# M8655B.net
KiCad netlist of a schematic drawn in EAGLE
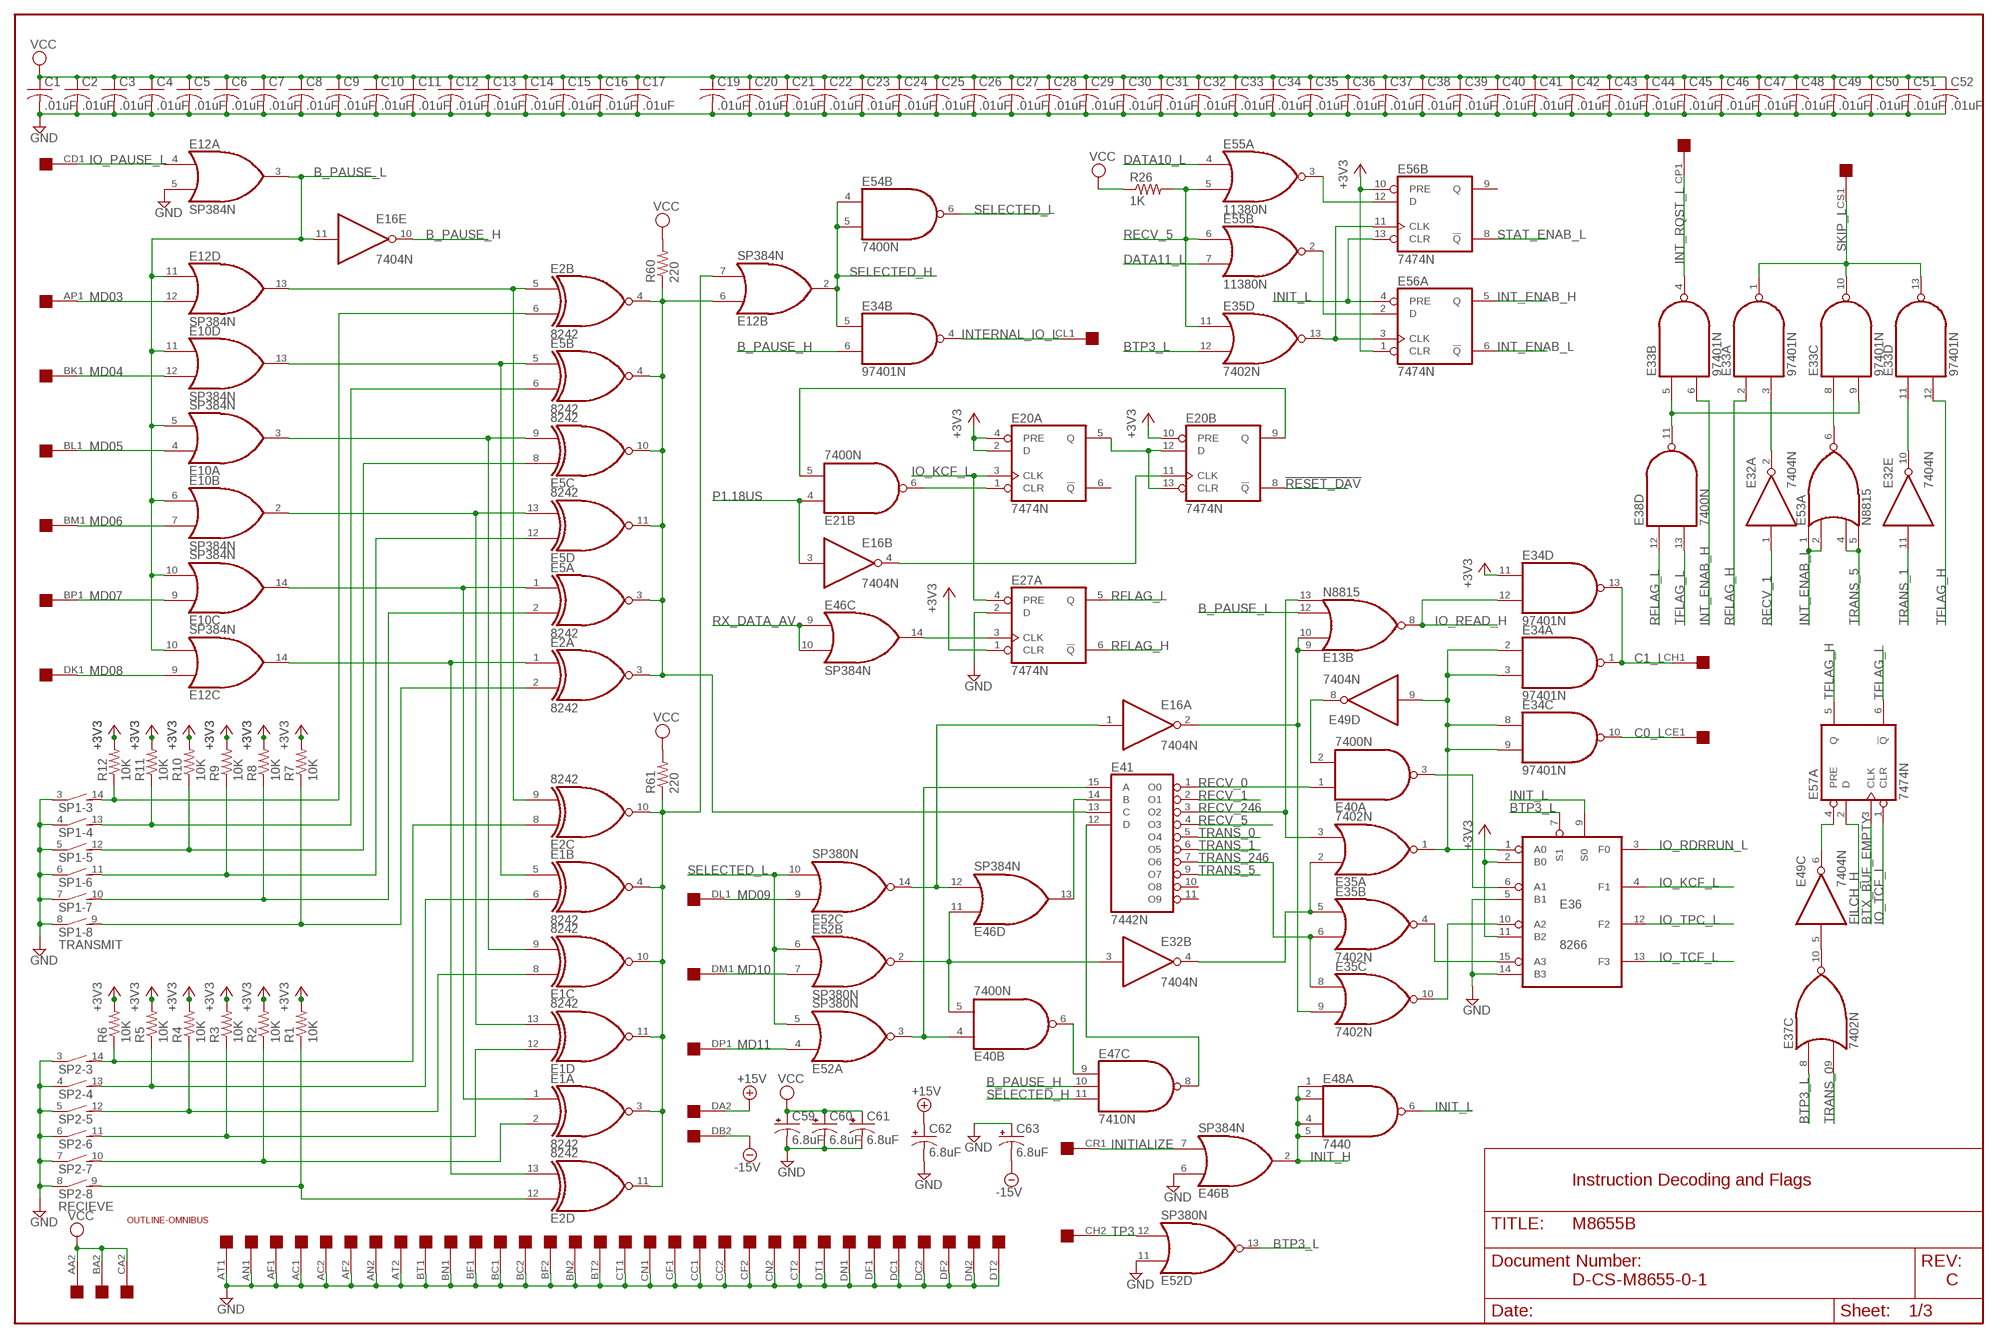
[diagram p0: schematic, sheet 1]
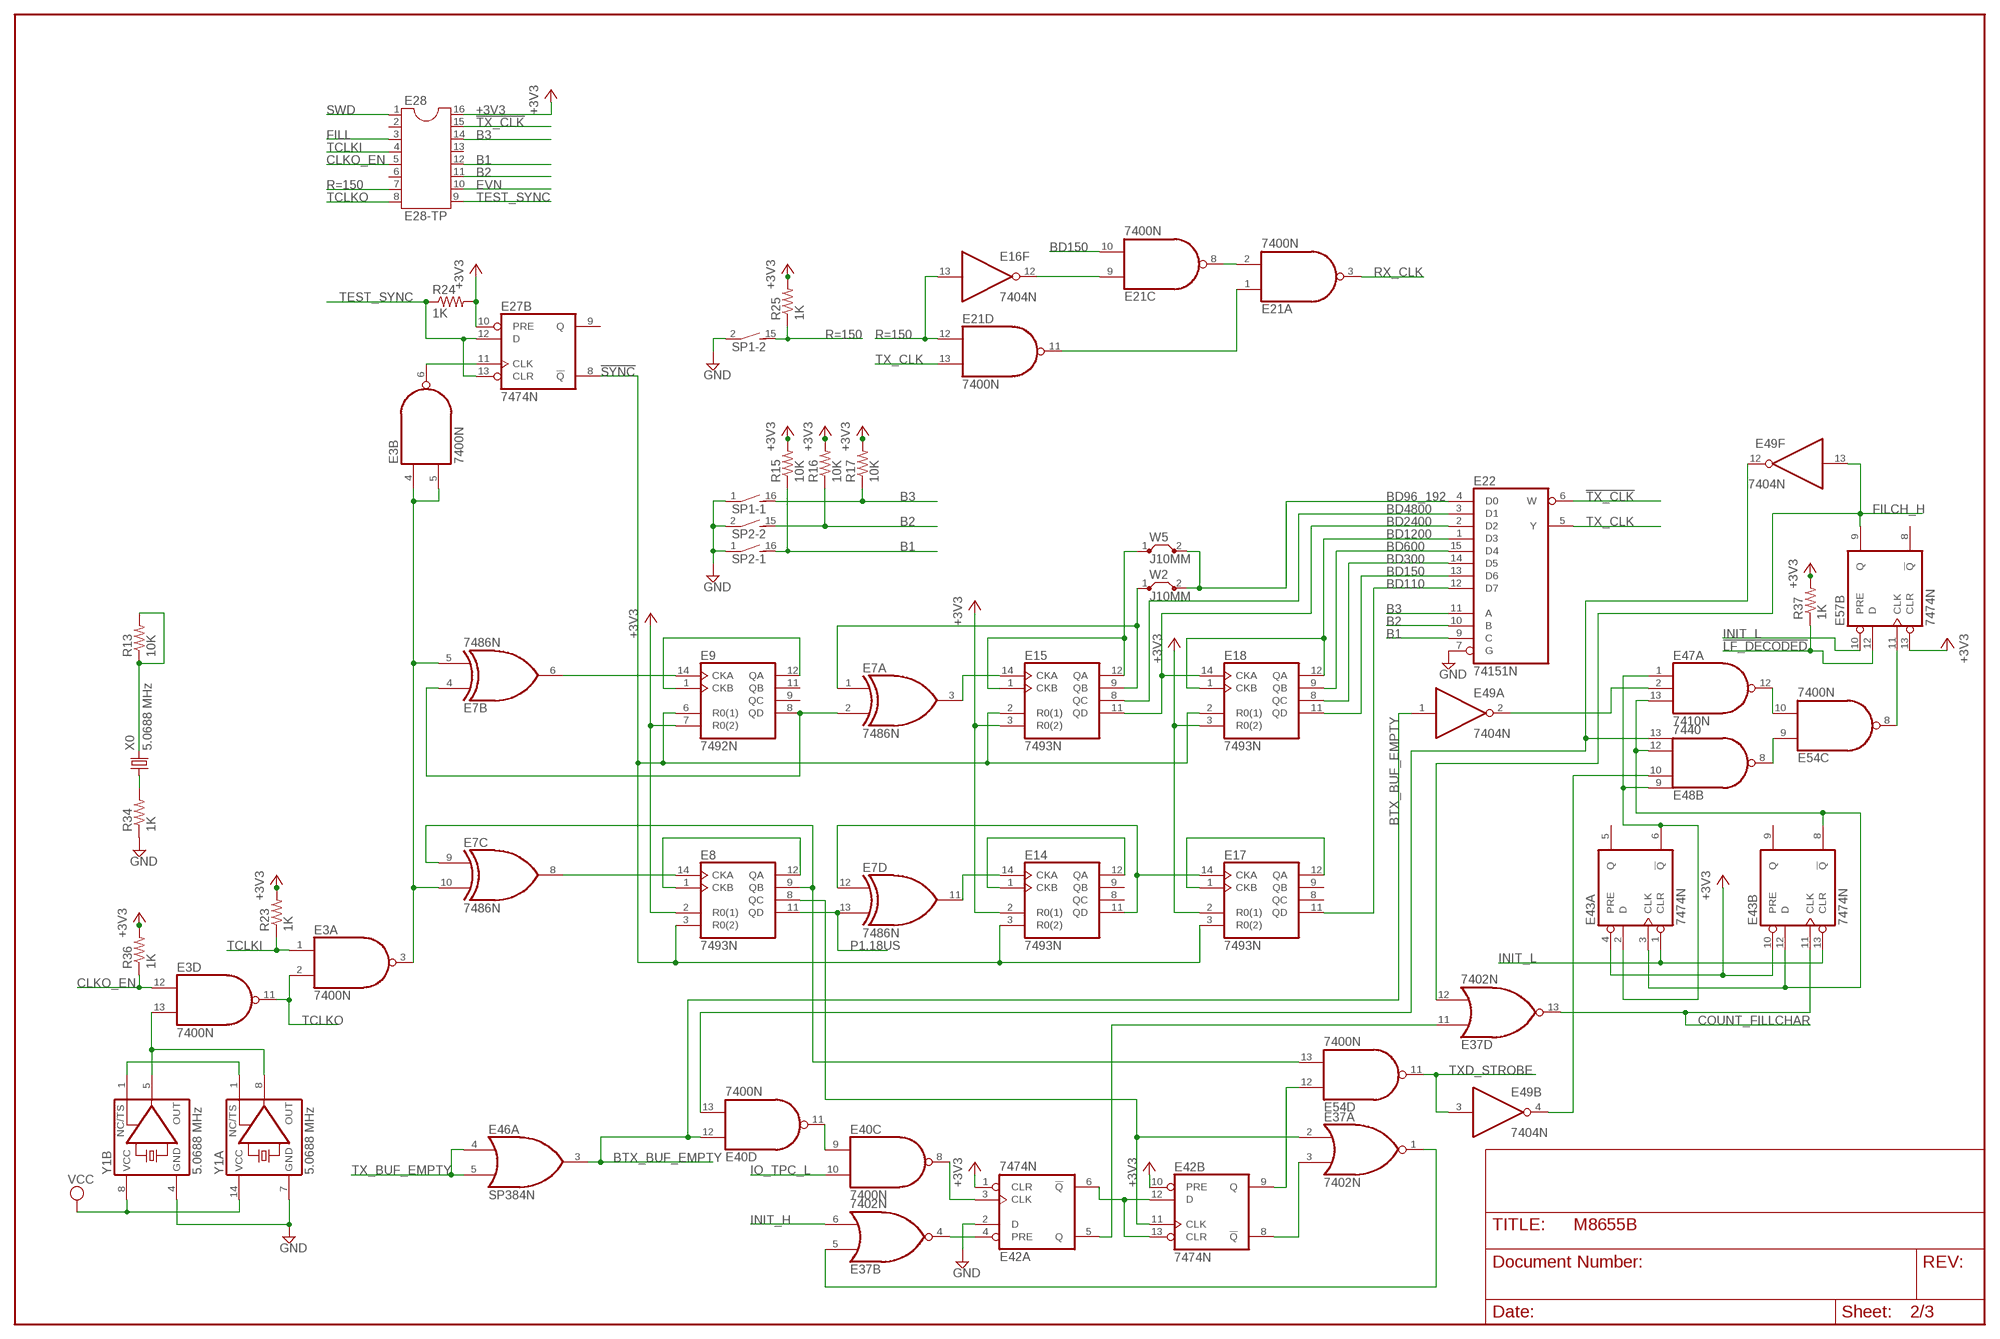
[diagram p1: schematic, sheet 2]
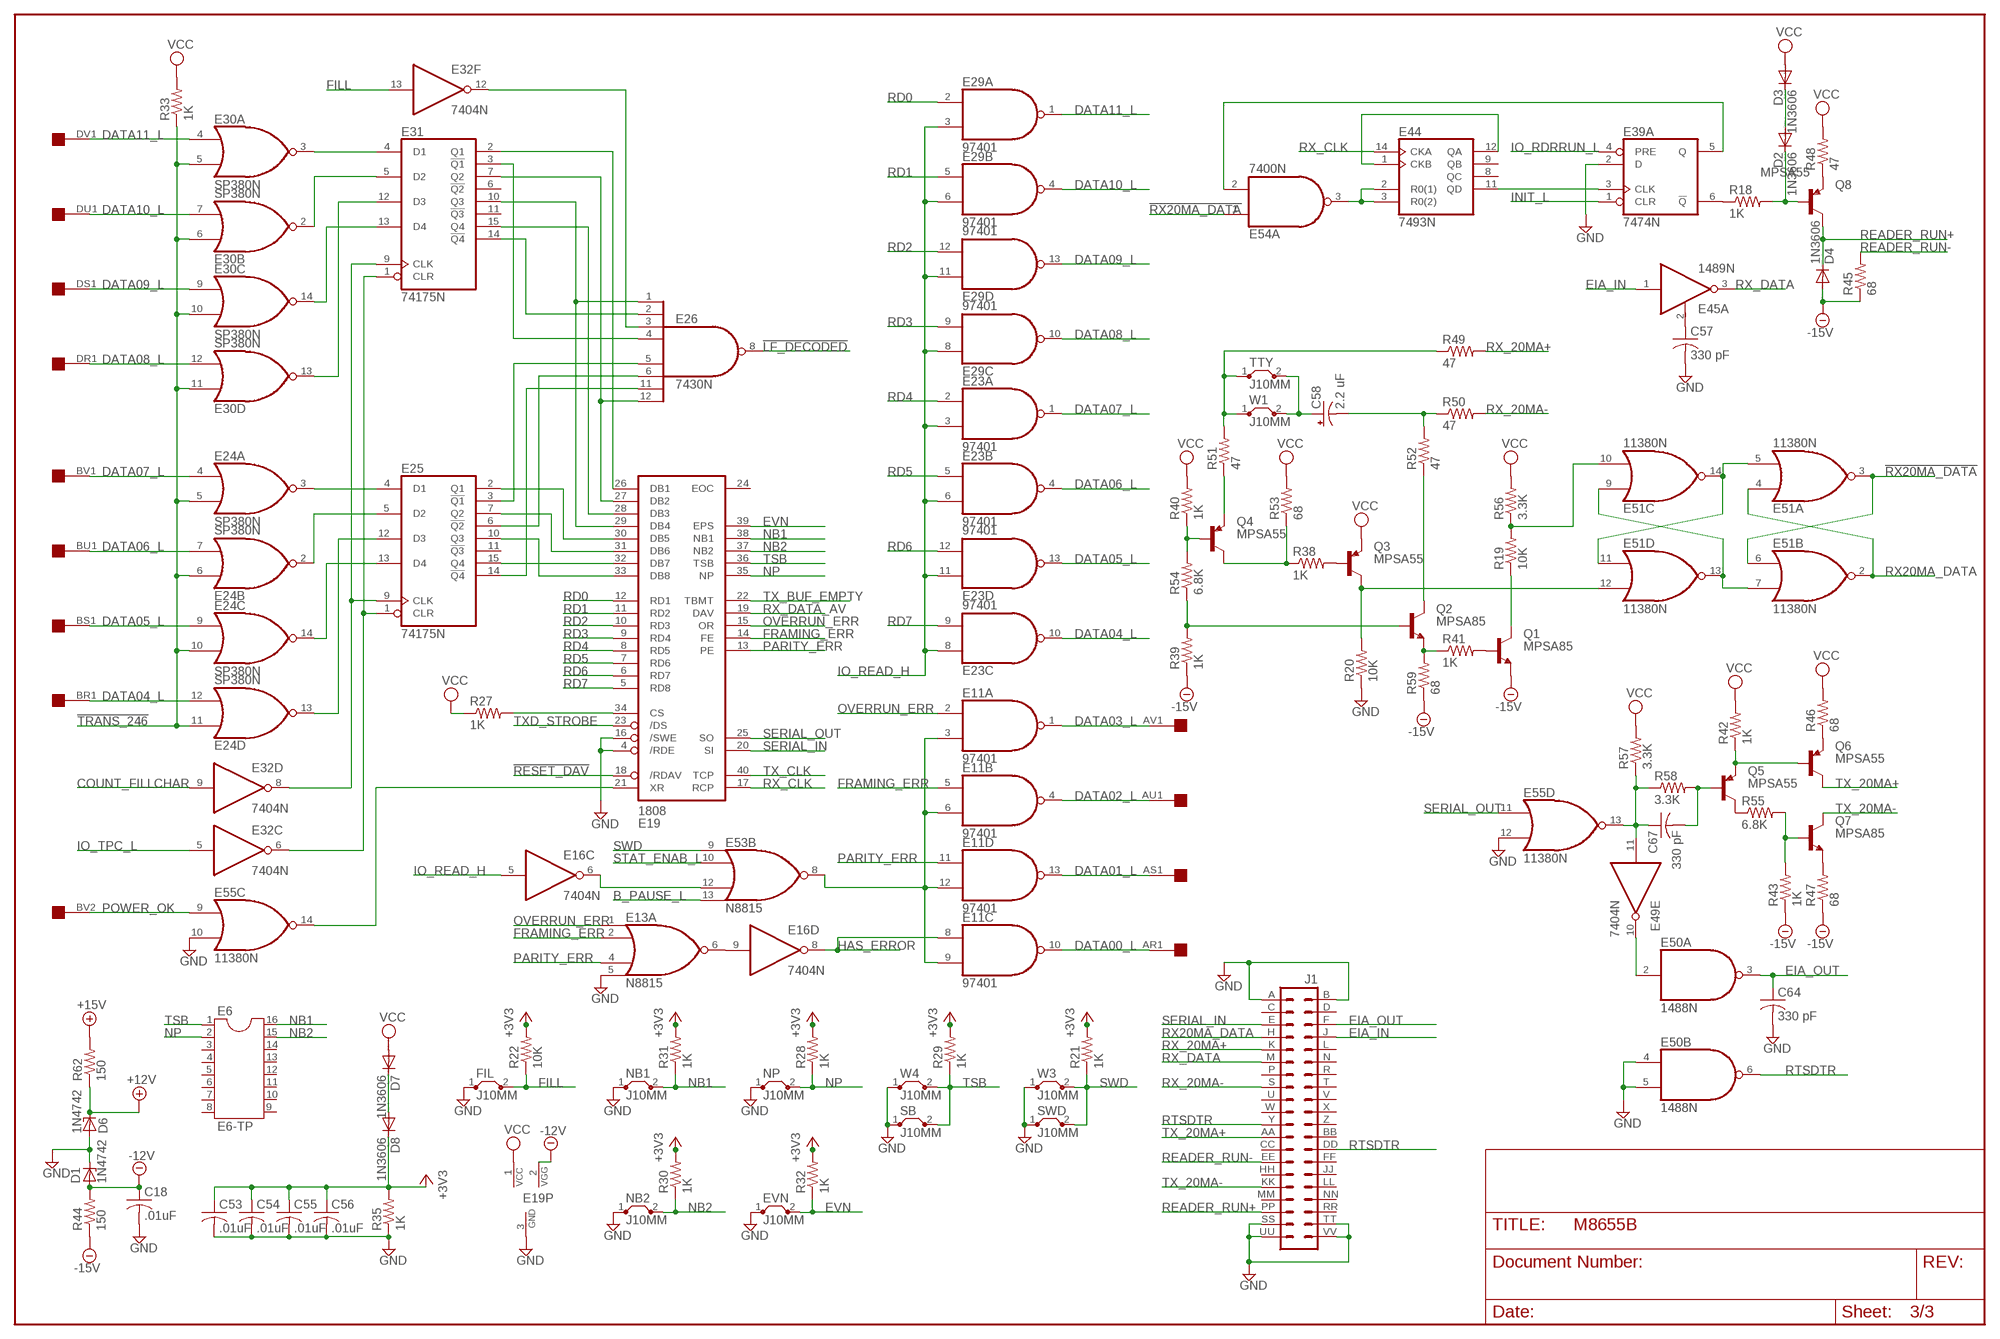
[diagram p2: schematic, sheet 3]

(export (version "E")
  (design (tool "Eeschema 10.0.6"))
  (components
    (comp (ref "C1")
      (value ".01uF")
      (footprint "eagle-import:C050-025X075")
      (libsource (lib "eagle-import") (part "C-US050-025X075"))
    )
    (comp (ref "C2")
      (value ".01uF")
      (footprint "eagle-import:C050-025X075")
      (libsource (lib "eagle-import") (part "C-US050-025X075"))
    )
    (comp (ref "C3")
      (value ".01uF")
      (footprint "eagle-import:C050-025X075")
      (libsource (lib "eagle-import") (part "C-US050-025X075"))
    )
    (comp (ref "C4")
      (value ".01uF")
      (footprint "eagle-import:C050-025X075")
      (libsource (lib "eagle-import") (part "C-US050-025X075"))
    )
    (comp (ref "C5")
      (value ".01uF")
      (footprint "eagle-import:C050-025X075")
      (libsource (lib "eagle-import") (part "C-US050-025X075"))
    )
    (comp (ref "C6")
      (value ".01uF")
      (footprint "eagle-import:C050-025X075")
      (libsource (lib "eagle-import") (part "C-US050-025X075"))
    )
    (comp (ref "C7")
      (value ".01uF")
      (footprint "eagle-import:C050-025X075")
      (libsource (lib "eagle-import") (part "C-US050-025X075"))
    )
    (comp (ref "C8")
      (value ".01uF")
      (footprint "eagle-import:C050-025X075")
      (libsource (lib "eagle-import") (part "C-US050-025X075"))
    )
    (comp (ref "C9")
      (value ".01uF")
      (footprint "eagle-import:C050-025X075")
      (libsource (lib "eagle-import") (part "C-US050-025X075"))
    )
    (comp (ref "C10")
      (value ".01uF")
      (footprint "eagle-import:C050-025X075")
      (libsource (lib "eagle-import") (part "C-US050-025X075"))
    )
    (comp (ref "C11")
      (value ".01uF")
      (footprint "eagle-import:C050-025X075")
      (libsource (lib "eagle-import") (part "C-US050-025X075"))
    )
    (comp (ref "C12")
      (value ".01uF")
      (footprint "eagle-import:C050-025X075")
      (libsource (lib "eagle-import") (part "C-US050-025X075"))
    )
    (comp (ref "C13")
      (value ".01uF")
      (footprint "eagle-import:C050-025X075")
      (libsource (lib "eagle-import") (part "C-US050-025X075"))
    )
    (comp (ref "C14")
      (value ".01uF")
      (footprint "eagle-import:C050-025X075")
      (libsource (lib "eagle-import") (part "C-US050-025X075"))
    )
    (comp (ref "C15")
      (value ".01uF")
      (footprint "eagle-import:C050-025X075")
      (libsource (lib "eagle-import") (part "C-US050-025X075"))
    )
    (comp (ref "C16")
      (value ".01uF")
      (footprint "eagle-import:C050-025X075")
      (libsource (lib "eagle-import") (part "C-US050-025X075"))
    )
    (comp (ref "C17")
      (value ".01uF")
      (footprint "eagle-import:C050-025X075")
      (libsource (lib "eagle-import") (part "C-US050-025X075"))
    )
    (comp (ref "C19")
      (value ".01uF")
      (footprint "eagle-import:C050-025X075")
      (libsource (lib "eagle-import") (part "C-US050-025X075"))
    )
    (comp (ref "C20")
      (value ".01uF")
      (footprint "eagle-import:C050-025X075")
      (libsource (lib "eagle-import") (part "C-US050-025X075"))
    )
    (comp (ref "C21")
      (value ".01uF")
      (footprint "eagle-import:C050-025X075")
      (libsource (lib "eagle-import") (part "C-US050-025X075"))
    )
    (comp (ref "C22")
      (value ".01uF")
      (footprint "eagle-import:C050-025X075")
      (libsource (lib "eagle-import") (part "C-US050-025X075"))
    )
    (comp (ref "C23")
      (value ".01uF")
      (footprint "eagle-import:C050-025X075")
      (libsource (lib "eagle-import") (part "C-US050-025X075"))
    )
    (comp (ref "C24")
      (value ".01uF")
      (footprint "eagle-import:C050-025X075")
      (libsource (lib "eagle-import") (part "C-US050-025X075"))
    )
    (comp (ref "C25")
      (value ".01uF")
      (footprint "eagle-import:C050-025X075")
      (libsource (lib "eagle-import") (part "C-US050-025X075"))
    )
    (comp (ref "C26")
      (value ".01uF")
      (footprint "eagle-import:C050-025X075")
      (libsource (lib "eagle-import") (part "C-US050-025X075"))
    )
    (comp (ref "C27")
      (value ".01uF")
      (footprint "eagle-import:C050-025X075")
      (libsource (lib "eagle-import") (part "C-US050-025X075"))
    )
    (comp (ref "C28")
      (value ".01uF")
      (footprint "eagle-import:C050-025X075")
      (libsource (lib "eagle-import") (part "C-US050-025X075"))
    )
    (comp (ref "C29")
      (value ".01uF")
      (footprint "eagle-import:C050-025X075")
      (libsource (lib "eagle-import") (part "C-US050-025X075"))
    )
    (comp (ref "C30")
      (value ".01uF")
      (footprint "eagle-import:C050-025X075")
      (libsource (lib "eagle-import") (part "C-US050-025X075"))
    )
    (comp (ref "C31")
      (value ".01uF")
      (footprint "eagle-import:C050-025X075")
      (libsource (lib "eagle-import") (part "C-US050-025X075"))
    )
    (comp (ref "C32")
      (value ".01uF")
      (footprint "eagle-import:C050-025X075")
      (libsource (lib "eagle-import") (part "C-US050-025X075"))
    )
    (comp (ref "C33")
      (value ".01uF")
      (footprint "eagle-import:C050-025X075")
      (libsource (lib "eagle-import") (part "C-US050-025X075"))
    )
    (comp (ref "C34")
      (value ".01uF")
      (footprint "eagle-import:C050-025X075")
      (libsource (lib "eagle-import") (part "C-US050-025X075"))
    )
    (comp (ref "C35")
      (value ".01uF")
      (footprint "eagle-import:C050-025X075")
      (libsource (lib "eagle-import") (part "C-US050-025X075"))
    )
    (comp (ref "C36")
      (value ".01uF")
      (footprint "eagle-import:C050-025X075")
      (libsource (lib "eagle-import") (part "C-US050-025X075"))
    )
    (comp (ref "C37")
      (value ".01uF")
      (footprint "eagle-import:C050-025X075")
      (libsource (lib "eagle-import") (part "C-US050-025X075"))
    )
    (comp (ref "C38")
      (value ".01uF")
      (footprint "eagle-import:C050-025X075")
      (libsource (lib "eagle-import") (part "C-US050-025X075"))
    )
    (comp (ref "C39")
      (value ".01uF")
      (footprint "eagle-import:C050-025X075")
      (libsource (lib "eagle-import") (part "C-US050-025X075"))
    )
    (comp (ref "C40")
      (value ".01uF")
      (footprint "eagle-import:C050-025X075")
      (libsource (lib "eagle-import") (part "C-US050-025X075"))
    )
    (comp (ref "C41")
      (value ".01uF")
      (footprint "eagle-import:C050-025X075")
      (libsource (lib "eagle-import") (part "C-US050-025X075"))
    )
    (comp (ref "C42")
      (value ".01uF")
      (footprint "eagle-import:C050-025X075")
      (libsource (lib "eagle-import") (part "C-US050-025X075"))
    )
    (comp (ref "C43")
      (value ".01uF")
      (footprint "eagle-import:C050-025X075")
      (libsource (lib "eagle-import") (part "C-US050-025X075"))
    )
    (comp (ref "C44")
      (value ".01uF")
      (footprint "eagle-import:C050-025X075")
      (libsource (lib "eagle-import") (part "C-US050-025X075"))
    )
    (comp (ref "C45")
      (value ".01uF")
      (footprint "eagle-import:C050-025X075")
      (libsource (lib "eagle-import") (part "C-US050-025X075"))
    )
    (comp (ref "C46")
      (value ".01uF")
      (footprint "eagle-import:C050-025X075")
      (libsource (lib "eagle-import") (part "C-US050-025X075"))
    )
    (comp (ref "C47")
      (value ".01uF")
      (footprint "eagle-import:C050-025X075")
      (libsource (lib "eagle-import") (part "C-US050-025X075"))
    )
    (comp (ref "C48")
      (value ".01uF")
      (footprint "eagle-import:C050-025X075")
      (libsource (lib "eagle-import") (part "C-US050-025X075"))
    )
    (comp (ref "C49")
      (value ".01uF")
      (footprint "eagle-import:C050-025X075")
      (libsource (lib "eagle-import") (part "C-US050-025X075"))
    )
    (comp (ref "C50")
      (value ".01uF")
      (footprint "eagle-import:C050-025X075")
      (libsource (lib "eagle-import") (part "C-US050-025X075"))
    )
    (comp (ref "C51")
      (value ".01uF")
      (footprint "eagle-import:C050-025X075")
      (libsource (lib "eagle-import") (part "C-US050-025X075"))
    )
    (comp (ref "C52")
      (value ".01uF")
      (footprint "eagle-import:C050-025X075")
      (libsource (lib "eagle-import") (part "C-US050-025X075"))
    )
    (comp (ref "C59")
      (value "6.8uF")
      (footprint "eagle-import:E12-8")
      (libsource (lib "eagle-import") (part "CPOL-USE20-8AXIAL"))
    )
    (comp (ref "C60")
      (value "6.8uF")
      (footprint "eagle-import:E12-8")
      (libsource (lib "eagle-import") (part "CPOL-USE20-8AXIAL"))
    )
    (comp (ref "C61")
      (value "6.8uF")
      (footprint "eagle-import:E12-8")
      (libsource (lib "eagle-import") (part "CPOL-USE20-8AXIAL"))
    )
    (comp (ref "C62")
      (value "6.8uF")
      (footprint "eagle-import:E12-8")
      (libsource (lib "eagle-import") (part "CPOL-USE20-8AXIAL"))
    )
    (comp (ref "C63")
      (value "6.8uF")
      (footprint "eagle-import:E12-8")
      (libsource (lib "eagle-import") (part "CPOL-USE20-8AXIAL"))
    )
    (comp (ref "E1")
      (value "8242")
      (footprint "eagle-import:DIL14")
      (libsource (lib "eagle-import") (part "74266NLS"))
    )
    (comp (ref "E2")
      (value "8242")
      (footprint "eagle-import:DIL14")
      (libsource (lib "eagle-import") (part "74266NLS"))
    )
    (comp (ref "E5")
      (value "8242")
      (footprint "eagle-import:DIL14")
      (libsource (lib "eagle-import") (part "74266NLS"))
    )
    (comp (ref "E10")
      (value "SP384N")
      (footprint "eagle-import:DIL14")
      (libsource (lib "eagle-import") (part "SP384N"))
    )
    (comp (ref "E12")
      (value "SP384N")
      (footprint "eagle-import:DIL14")
      (libsource (lib "eagle-import") (part "SP384N"))
    )
    (comp (ref "E13")
      (value "N8815")
      (footprint "eagle-import:DIL14")
      (libsource (lib "eagle-import") (part "N8815"))
    )
    (comp (ref "E16")
      (value "7404N")
      (footprint "eagle-import:DIL14")
      (libsource (lib "eagle-import") (part "7404N"))
    )
    (comp (ref "E20")
      (value "7474N")
      (footprint "eagle-import:DIL14")
      (libsource (lib "eagle-import") (part "7474NS"))
    )
    (comp (ref "E21")
      (value "7400N")
      (footprint "eagle-import:DIL14")
      (libsource (lib "eagle-import") (part "7400N"))
    )
    (comp (ref "E27")
      (value "7474N")
      (footprint "eagle-import:DIL14")
      (libsource (lib "eagle-import") (part "7474NS"))
    )
    (comp (ref "E32")
      (value "7404N")
      (footprint "eagle-import:DIL14")
      (libsource (lib "eagle-import") (part "7404N"))
    )
    (comp (ref "E33")
      (value "97401N")
      (footprint "eagle-import:DIL14")
      (libsource (lib "eagle-import") (part "7401NLS"))
    )
    (comp (ref "E34")
      (value "97401N")
      (footprint "eagle-import:DIL14")
      (libsource (lib "eagle-import") (part "7401NLS"))
    )
    (comp (ref "E35")
      (value "7402N")
      (footprint "eagle-import:DIL14")
      (libsource (lib "eagle-import") (part "7402N"))
    )
    (comp (ref "E36")
      (value "8266")
      (footprint "eagle-import:DIL16")
      (libsource (lib "eagle-import") (part "8266"))
    )
    (comp (ref "E37")
      (value "7402N")
      (footprint "eagle-import:DIL14")
      (libsource (lib "eagle-import") (part "7402N"))
    )
    (comp (ref "E38")
      (value "7400N")
      (footprint "eagle-import:DIL14")
      (libsource (lib "eagle-import") (part "7400N"))
    )
    (comp (ref "E40")
      (value "7400N")
      (footprint "eagle-import:DIL14")
      (libsource (lib "eagle-import") (part "7400N"))
    )
    (comp (ref "E41")
      (value "7442N")
      (footprint "eagle-import:DIL16")
      (libsource (lib "eagle-import") (part "7442NLS"))
    )
    (comp (ref "E46")
      (value "SP384N")
      (footprint "eagle-import:DIL14")
      (libsource (lib "eagle-import") (part "SP384N"))
    )
    (comp (ref "E47")
      (value "7410N")
      (footprint "eagle-import:DIL14")
      (libsource (lib "eagle-import") (part "7410N"))
    )
    (comp (ref "E48")
      (value "7440")
      (footprint "eagle-import:DIL14")
      (libsource (lib "eagle-import") (part "7420NS"))
    )
    (comp (ref "E49")
      (value "7404N")
      (footprint "eagle-import:DIL14")
      (libsource (lib "eagle-import") (part "7404N"))
    )
    (comp (ref "E52")
      (value "SP380N")
      (footprint "eagle-import:DIL14")
      (libsource (lib "eagle-import") (part "SP380N"))
    )
    (comp (ref "E53")
      (value "N8815")
      (footprint "eagle-import:DIL14")
      (libsource (lib "eagle-import") (part "N8815"))
    )
    (comp (ref "E54")
      (value "7400N")
      (footprint "eagle-import:DIL14")
      (libsource (lib "eagle-import") (part "7400N"))
    )
    (comp (ref "E55")
      (value "11380N")
      (footprint "eagle-import:DIL14")
      (libsource (lib "eagle-import") (part "SP380N"))
    )
    (comp (ref "E56")
      (value "7474N")
      (footprint "eagle-import:DIL14")
      (libsource (lib "eagle-import") (part "7474NS"))
    )
    (comp (ref "E57")
      (value "7474N")
      (footprint "eagle-import:DIL14")
      (libsource (lib "eagle-import") (part "7474NS"))
    )
    (comp (ref "R1")
      (value "10K")
      (footprint "eagle-import:0207_10")
      (libsource (lib "eagle-import") (part "R-US_0207/10"))
    )
    (comp (ref "R2")
      (value "10K")
      (footprint "eagle-import:0207_10")
      (libsource (lib "eagle-import") (part "R-US_0207/10"))
    )
    (comp (ref "R3")
      (value "10K")
      (footprint "eagle-import:0207_10")
      (libsource (lib "eagle-import") (part "R-US_0207/10"))
    )
    (comp (ref "R4")
      (value "10K")
      (footprint "eagle-import:0207_10")
      (libsource (lib "eagle-import") (part "R-US_0207/10"))
    )
    (comp (ref "R5")
      (value "10K")
      (footprint "eagle-import:0207_10")
      (libsource (lib "eagle-import") (part "R-US_0207/10"))
    )
    (comp (ref "R6")
      (value "10K")
      (footprint "eagle-import:0207_10")
      (libsource (lib "eagle-import") (part "R-US_0207/10"))
    )
    (comp (ref "R7")
      (value "10K")
      (footprint "eagle-import:0207_10")
      (libsource (lib "eagle-import") (part "R-US_0207/10"))
    )
    (comp (ref "R8")
      (value "10K")
      (footprint "eagle-import:0207_10")
      (libsource (lib "eagle-import") (part "R-US_0207/10"))
    )
    (comp (ref "R9")
      (value "10K")
      (footprint "eagle-import:0207_10")
      (libsource (lib "eagle-import") (part "R-US_0207/10"))
    )
    (comp (ref "R10")
      (value "10K")
      (footprint "eagle-import:0207_10")
      (libsource (lib "eagle-import") (part "R-US_0207/10"))
    )
    (comp (ref "R11")
      (value "10K")
      (footprint "eagle-import:0207_10")
      (libsource (lib "eagle-import") (part "R-US_0207/10"))
    )
    (comp (ref "R12")
      (value "10K")
      (footprint "eagle-import:0207_10")
      (libsource (lib "eagle-import") (part "R-US_0207/10"))
    )
    (comp (ref "R26")
      (value "1K")
      (footprint "eagle-import:0207_10")
      (libsource (lib "eagle-import") (part "R-US_0207/10"))
    )
    (comp (ref "R60")
      (value "220")
      (footprint "eagle-import:0207_10")
      (libsource (lib "eagle-import") (part "R-US_0207/10"))
    )
    (comp (ref "R61")
      (value "220")
      (footprint "eagle-import:0207_10")
      (libsource (lib "eagle-import") (part "R-US_0207/10"))
    )
    (comp (ref "SP1")
      (value "TRANSMIT")
      (footprint "eagle-import:DIP08S")
      (libsource (lib "eagle-import") (part "DIP08S"))
    )
    (comp (ref "SP2")
      (value "RECIEVE")
      (footprint "eagle-import:DIP08S")
      (libsource (lib "eagle-import") (part "DIP08S"))
    )
    (comp (ref "U$1")
      (value "OUTLINE-OMNIBUS")
      (footprint "eagle-import:OMNIBUS")
      (libsource (lib "eagle-import") (part "OUTLINE-OMNIBUS"))
    )
    (comp (ref "U$2")
      (value "QUAD")
      (footprint "eagle-import:EDGE-CON8")
      (libsource (lib "eagle-import") (part "QUAD"))
    )
    (comp (ref "E3")
      (value "7400N")
      (footprint "eagle-import:DIL14")
      (libsource (lib "eagle-import") (part "7400N"))
    )
    (comp (ref "E7")
      (value "7486N")
      (footprint "eagle-import:DIL14")
      (libsource (lib "eagle-import") (part "7486N"))
    )
    (comp (ref "E8")
      (value "7493N")
      (footprint "eagle-import:DIL14")
      (libsource (lib "eagle-import") (part "7493NLS"))
    )
    (comp (ref "E9")
      (value "7492N")
      (footprint "eagle-import:DIL14")
      (libsource (lib "eagle-import") (part "7492NLS"))
    )
    (comp (ref "E14")
      (value "7493N")
      (footprint "eagle-import:DIL14")
      (libsource (lib "eagle-import") (part "7493NLS"))
    )
    (comp (ref "E15")
      (value "7493N")
      (footprint "eagle-import:DIL14")
      (libsource (lib "eagle-import") (part "7493NLS"))
    )
    (comp (ref "E17")
      (value "7493N")
      (footprint "eagle-import:DIL14")
      (libsource (lib "eagle-import") (part "7493NLS"))
    )
    (comp (ref "E18")
      (value "7493N")
      (footprint "eagle-import:DIL14")
      (libsource (lib "eagle-import") (part "7493NLS"))
    )
    (comp (ref "E22")
      (value "74151N")
      (footprint "eagle-import:DIL16")
      (libsource (lib "eagle-import") (part "74151N"))
    )
    (comp (ref "E28")
      (value "E28-TP")
      (footprint "eagle-import:SOCKET-16")
      (libsource (lib "eagle-import") (part "DIL16S"))
    )
    (comp (ref "E42")
      (value "7474N")
      (footprint "eagle-import:DIL14")
      (libsource (lib "eagle-import") (part "7474NS"))
    )
    (comp (ref "E43")
      (value "7474N")
      (footprint "eagle-import:DIL14")
      (libsource (lib "eagle-import") (part "7474NS"))
    )
    (comp (ref "R13")
      (value "10K")
      (footprint "eagle-import:0207_10")
      (libsource (lib "eagle-import") (part "R-US_0207/10"))
    )
    (comp (ref "R15")
      (value "10K")
      (footprint "eagle-import:0207_10")
      (libsource (lib "eagle-import") (part "R-US_0207/10"))
    )
    (comp (ref "R16")
      (value "10K")
      (footprint "eagle-import:0207_10")
      (libsource (lib "eagle-import") (part "R-US_0207/10"))
    )
    (comp (ref "R17")
      (value "10K")
      (footprint "eagle-import:0207_10")
      (libsource (lib "eagle-import") (part "R-US_0207/10"))
    )
    (comp (ref "R23")
      (value "1K")
      (footprint "eagle-import:0207_10")
      (libsource (lib "eagle-import") (part "R-US_0207/10"))
    )
    (comp (ref "R24")
      (value "1K")
      (footprint "eagle-import:0207_10")
      (libsource (lib "eagle-import") (part "R-US_0207/10"))
    )
    (comp (ref "R25")
      (value "1K")
      (footprint "eagle-import:0207_10")
      (libsource (lib "eagle-import") (part "R-US_0207/10"))
    )
    (comp (ref "R34")
      (value "1K")
      (footprint "eagle-import:0207_10")
      (libsource (lib "eagle-import") (part "R-US_0207/10"))
    )
    (comp (ref "R36")
      (value "1K")
      (footprint "eagle-import:0207_10")
      (libsource (lib "eagle-import") (part "R-US_0207/10"))
    )
    (comp (ref "R37")
      (value "1K")
      (footprint "eagle-import:0207_10")
      (libsource (lib "eagle-import") (part "R-US_0207/10"))
    )
    (comp (ref "W2")
      (value "J10MM")
      (footprint "eagle-import:10")
      (libsource (lib "eagle-import") (part "J10MM"))
    )
    (comp (ref "W5")
      (value "J10MM")
      (footprint "eagle-import:10")
      (libsource (lib "eagle-import") (part "J10MM"))
    )
    (comp (ref "X0")
      (value "5.0688 MHz")
      (footprint "eagle-import:HC33U-H")
      (libsource (lib "eagle-import") (part "CRYSTALHC33U-H"))
    )
    (comp (ref "Y1A")
      (value "5.0688 MHz")
      (footprint "eagle-import:DIL14S")
      (libsource (lib "eagle-import") (part "XO-14"))
    )
    (comp (ref "Y1B")
      (value "5.0688 MHz")
      (footprint "eagle-import:DIL08S")
      (libsource (lib "eagle-import") (part "XO-8"))
    )
    (comp (ref "C18")
      (value ".01uF")
      (footprint "eagle-import:C050-025X075")
      (libsource (lib "eagle-import") (part "C-US050-025X075"))
    )
    (comp (ref "C53")
      (value ".01uF")
      (footprint "eagle-import:C050-025X075")
      (libsource (lib "eagle-import") (part "C-US050-025X075"))
    )
    (comp (ref "C54")
      (value ".01uF")
      (footprint "eagle-import:C050-025X075")
      (libsource (lib "eagle-import") (part "C-US050-025X075"))
    )
    (comp (ref "C55")
      (value ".01uF")
      (footprint "eagle-import:C050-025X075")
      (libsource (lib "eagle-import") (part "C-US050-025X075"))
    )
    (comp (ref "C56")
      (value ".01uF")
      (footprint "eagle-import:C050-025X075")
      (libsource (lib "eagle-import") (part "C-US050-025X075"))
    )
    (comp (ref "C57")
      (value "330 pF")
      (footprint "eagle-import:C050-025X075")
      (libsource (lib "eagle-import") (part "C-US050-025X075"))
    )
    (comp (ref "C58")
      (value "2.2 uF")
      (footprint "eagle-import:E12-8")
      (libsource (lib "eagle-import") (part "CPOL-USE20-8AXIAL"))
    )
    (comp (ref "C64")
      (value "330 pF")
      (footprint "eagle-import:C050-025X075")
      (libsource (lib "eagle-import") (part "C-US050-025X075"))
    )
    (comp (ref "C67")
      (value "330 pF")
      (footprint "eagle-import:C050-025X075")
      (libsource (lib "eagle-import") (part "C-US050-025X075"))
    )
    (comp (ref "D1")
      (value "1N4742")
      (footprint "eagle-import:DO41Z10")
      (libsource (lib "eagle-import") (part "ZENER-DIODEDO41Z10"))
    )
    (comp (ref "D2")
      (value "1N3606")
      (footprint "eagle-import:DO35-10")
      (libsource (lib "eagle-import") (part "DIODE-DO35-10"))
    )
    (comp (ref "D3")
      (value "1N3606")
      (footprint "eagle-import:DO35-10")
      (libsource (lib "eagle-import") (part "DIODE-DO35-10"))
    )
    (comp (ref "D4")
      (value "1N3606")
      (footprint "eagle-import:DO35-10")
      (libsource (lib "eagle-import") (part "DIODE-DO35-10"))
    )
    (comp (ref "D6")
      (value "1N4742")
      (footprint "eagle-import:DO41Z10")
      (libsource (lib "eagle-import") (part "ZENER-DIODEDO41Z10"))
    )
    (comp (ref "D7")
      (value "1N3606")
      (footprint "eagle-import:DO35-10")
      (libsource (lib "eagle-import") (part "DIODE-DO35-10"))
    )
    (comp (ref "D8")
      (value "1N3606")
      (footprint "eagle-import:DO35-10")
      (libsource (lib "eagle-import") (part "DIODE-DO35-10"))
    )
    (comp (ref "E6")
      (value "E6-TP")
      (footprint "eagle-import:SOCKET-16")
      (libsource (lib "eagle-import") (part "DIL16S"))
    )
    (comp (ref "E11")
      (value "97401")
      (footprint "eagle-import:DIL14")
      (libsource (lib "eagle-import") (part "7401NLS"))
    )
    (comp (ref "E19")
      (value "1808")
      (footprint "eagle-import:DIL40")
      (libsource (lib "eagle-import") (part "AY-5-1013A"))
    )
    (comp (ref "E23")
      (value "97401")
      (footprint "eagle-import:DIL14")
      (libsource (lib "eagle-import") (part "7401NLS"))
    )
    (comp (ref "E24")
      (value "SP380N")
      (footprint "eagle-import:DIL14")
      (libsource (lib "eagle-import") (part "SP380N"))
    )
    (comp (ref "E25")
      (value "74175N")
      (footprint "eagle-import:DIL16")
      (libsource (lib "eagle-import") (part "74175N"))
    )
    (comp (ref "E26")
      (value "7430N")
      (footprint "eagle-import:DIL14")
      (libsource (lib "eagle-import") (part "7430N"))
    )
    (comp (ref "E29")
      (value "97401")
      (footprint "eagle-import:DIL14")
      (libsource (lib "eagle-import") (part "7401NLS"))
    )
    (comp (ref "E30")
      (value "SP380N")
      (footprint "eagle-import:DIL14")
      (libsource (lib "eagle-import") (part "SP380N"))
    )
    (comp (ref "E31")
      (value "74175N")
      (footprint "eagle-import:DIL16")
      (libsource (lib "eagle-import") (part "74175N"))
    )
    (comp (ref "E39")
      (value "7474N")
      (footprint "eagle-import:DIL14")
      (libsource (lib "eagle-import") (part "7474NS"))
    )
    (comp (ref "E44")
      (value "7493N")
      (footprint "eagle-import:DIL14")
      (libsource (lib "eagle-import") (part "7493NLS"))
    )
    (comp (ref "E45")
      (value "1489N")
      (footprint "eagle-import:DIL14")
      (libsource (lib "eagle-import") (part "1489N"))
    )
    (comp (ref "E50")
      (value "1488N")
      (footprint "eagle-import:DIL14")
      (libsource (lib "eagle-import") (part "1488N"))
    )
    (comp (ref "E51")
      (value "11380N")
      (footprint "eagle-import:DIL14")
      (libsource (lib "eagle-import") (part "SP380N"))
    )
    (comp (ref "EVN")
      (value "J10MM")
      (footprint "eagle-import:10")
      (libsource (lib "eagle-import") (part "J10MM"))
    )
    (comp (ref "FIL")
      (value "J10MM")
      (footprint "eagle-import:10")
      (libsource (lib "eagle-import") (part "J10MM"))
    )
    (comp (ref "J1")
      (value "DEC40PINH")
      (footprint "eagle-import:DEC40PINH")
      (libsource (lib "eagle-import") (part "DEC40PINH"))
    )
    (comp (ref "NB1")
      (value "J10MM")
      (footprint "eagle-import:10")
      (libsource (lib "eagle-import") (part "J10MM"))
    )
    (comp (ref "NB2")
      (value "J10MM")
      (footprint "eagle-import:10")
      (libsource (lib "eagle-import") (part "J10MM"))
    )
    (comp (ref "NP")
      (value "J10MM")
      (footprint "eagle-import:10")
      (libsource (lib "eagle-import") (part "J10MM"))
    )
    (comp (ref "Q1")
      (value "MPSA85")
      (footprint "eagle-import:TO5")
      (libsource (lib "eagle-import") (part "-NPN-TO5"))
    )
    (comp (ref "Q2")
      (value "MPSA85")
      (footprint "eagle-import:TO5")
      (libsource (lib "eagle-import") (part "-NPN-TO5"))
    )
    (comp (ref "Q3")
      (value "MPSA55")
      (footprint "eagle-import:TO5")
      (libsource (lib "eagle-import") (part "-PNP-TO5"))
    )
    (comp (ref "Q4")
      (value "MPSA55")
      (footprint "eagle-import:TO5")
      (libsource (lib "eagle-import") (part "-PNP-TO5"))
    )
    (comp (ref "Q5")
      (value "MPSA55")
      (footprint "eagle-import:TO5")
      (libsource (lib "eagle-import") (part "-PNP-TO5"))
    )
    (comp (ref "Q6")
      (value "MPSA55")
      (footprint "eagle-import:TO5")
      (libsource (lib "eagle-import") (part "-PNP-TO5"))
    )
    (comp (ref "Q7")
      (value "MPSA85")
      (footprint "eagle-import:TO5")
      (libsource (lib "eagle-import") (part "-NPN-TO5"))
    )
    (comp (ref "Q8")
      (value "MPSA55")
      (footprint "eagle-import:TO5")
      (libsource (lib "eagle-import") (part "-PNP-TO5"))
    )
    (comp (ref "R18")
      (value "1K")
      (footprint "eagle-import:0207_10")
      (libsource (lib "eagle-import") (part "R-US_0207/10"))
    )
    (comp (ref "R19")
      (value "10K")
      (footprint "eagle-import:0207_10")
      (libsource (lib "eagle-import") (part "R-US_0207/10"))
    )
    (comp (ref "R20")
      (value "10K")
      (footprint "eagle-import:0207_10")
      (libsource (lib "eagle-import") (part "R-US_0207/10"))
    )
    (comp (ref "R21")
      (value "1K")
      (footprint "eagle-import:0207_10")
      (libsource (lib "eagle-import") (part "R-US_0207/10"))
    )
    (comp (ref "R22")
      (value "10K")
      (footprint "eagle-import:0207_10")
      (libsource (lib "eagle-import") (part "R-US_0207/10"))
    )
    (comp (ref "R27")
      (value "1K")
      (footprint "eagle-import:0207_10")
      (libsource (lib "eagle-import") (part "R-US_0207/10"))
    )
    (comp (ref "R28")
      (value "1K")
      (footprint "eagle-import:0207_10")
      (libsource (lib "eagle-import") (part "R-US_0207/10"))
    )
    (comp (ref "R29")
      (value "1K")
      (footprint "eagle-import:0207_10")
      (libsource (lib "eagle-import") (part "R-US_0207/10"))
    )
    (comp (ref "R30")
      (value "1K")
      (footprint "eagle-import:0207_10")
      (libsource (lib "eagle-import") (part "R-US_0207/10"))
    )
    (comp (ref "R31")
      (value "1K")
      (footprint "eagle-import:0207_10")
      (libsource (lib "eagle-import") (part "R-US_0207/10"))
    )
    (comp (ref "R32")
      (value "1K")
      (footprint "eagle-import:0207_10")
      (libsource (lib "eagle-import") (part "R-US_0207/10"))
    )
    (comp (ref "R33")
      (value "1K")
      (footprint "eagle-import:0207_10")
      (libsource (lib "eagle-import") (part "R-US_0207/10"))
    )
    (comp (ref "R35")
      (value "1K")
      (footprint "eagle-import:0207_10")
      (libsource (lib "eagle-import") (part "R-US_0207/10"))
    )
    (comp (ref "R38")
      (value "1K")
      (footprint "eagle-import:0207_10")
      (libsource (lib "eagle-import") (part "R-US_0207/10"))
    )
    (comp (ref "R39")
      (value "1K")
      (footprint "eagle-import:0207_10")
      (libsource (lib "eagle-import") (part "R-US_0207/10"))
    )
    (comp (ref "R40")
      (value "1K")
      (footprint "eagle-import:0207_10")
      (libsource (lib "eagle-import") (part "R-US_0207/10"))
    )
    (comp (ref "R41")
      (value "1K")
      (footprint "eagle-import:0207_10")
      (libsource (lib "eagle-import") (part "R-US_0207/10"))
    )
    (comp (ref "R42")
      (value "1K")
      (footprint "eagle-import:0207_10")
      (libsource (lib "eagle-import") (part "R-US_0207/10"))
    )
    (comp (ref "R43")
      (value "1K")
      (footprint "eagle-import:0207_10")
      (libsource (lib "eagle-import") (part "R-US_0207/10"))
    )
    (comp (ref "R44")
      (value "150")
      (footprint "eagle-import:0207_10")
      (libsource (lib "eagle-import") (part "R-US_0207/10"))
    )
    (comp (ref "R45")
      (value "68")
      (footprint "eagle-import:0207_10")
      (libsource (lib "eagle-import") (part "R-US_0207/10"))
    )
    (comp (ref "R46")
      (value "68")
      (footprint "eagle-import:0207_10")
      (libsource (lib "eagle-import") (part "R-US_0207/10"))
    )
    (comp (ref "R47")
      (value "68")
      (footprint "eagle-import:0207_10")
      (libsource (lib "eagle-import") (part "R-US_0207/10"))
    )
    (comp (ref "R48")
      (value "47")
      (footprint "eagle-import:0207_10")
      (libsource (lib "eagle-import") (part "R-US_0207/10"))
    )
    (comp (ref "R49")
      (value "47")
      (footprint "eagle-import:0207_10")
      (libsource (lib "eagle-import") (part "R-US_0207/10"))
    )
    (comp (ref "R50")
      (value "47")
      (footprint "eagle-import:0207_10")
      (libsource (lib "eagle-import") (part "R-US_0207/10"))
    )
    (comp (ref "R51")
      (value "47")
      (footprint "eagle-import:0207_10")
      (libsource (lib "eagle-import") (part "R-US_0207/10"))
    )
    (comp (ref "R52")
      (value "47")
      (footprint "eagle-import:0207_10")
      (libsource (lib "eagle-import") (part "R-US_0207/10"))
    )
    (comp (ref "R53")
      (value "68")
      (footprint "eagle-import:0207_10")
      (libsource (lib "eagle-import") (part "R-US_0207/10"))
    )
    (comp (ref "R54")
      (value "6.8K")
      (footprint "eagle-import:0207_10")
      (libsource (lib "eagle-import") (part "R-US_0207/10"))
    )
    (comp (ref "R55")
      (value "6.8K")
      (footprint "eagle-import:0207_10")
      (libsource (lib "eagle-import") (part "R-US_0207/10"))
    )
    (comp (ref "R56")
      (value "3.3K")
      (footprint "eagle-import:0207_10")
      (libsource (lib "eagle-import") (part "R-US_0207/10"))
    )
    (comp (ref "R57")
      (value "3.3K")
      (footprint "eagle-import:0207_10")
      (libsource (lib "eagle-import") (part "R-US_0207/10"))
    )
    (comp (ref "R58")
      (value "3.3K")
      (footprint "eagle-import:0207_10")
      (libsource (lib "eagle-import") (part "R-US_0207/10"))
    )
    (comp (ref "R59")
      (value "68")
      (footprint "eagle-import:0207_10")
      (libsource (lib "eagle-import") (part "R-US_0207/10"))
    )
    (comp (ref "R62")
      (value "150")
      (footprint "eagle-import:0207_10")
      (libsource (lib "eagle-import") (part "R-US_0207/10"))
    )
    (comp (ref "SB")
      (value "J10MM")
      (footprint "eagle-import:10")
      (libsource (lib "eagle-import") (part "J10MM"))
    )
    (comp (ref "SWD")
      (value "J10MM")
      (footprint "eagle-import:10")
      (libsource (lib "eagle-import") (part "J10MM"))
    )
    (comp (ref "TTY")
      (value "J10MM")
      (footprint "eagle-import:10")
      (libsource (lib "eagle-import") (part "J10MM"))
    )
    (comp (ref "W1")
      (value "J10MM")
      (footprint "eagle-import:10")
      (libsource (lib "eagle-import") (part "J10MM"))
    )
    (comp (ref "W3")
      (value "J10MM")
      (footprint "eagle-import:10")
      (libsource (lib "eagle-import") (part "J10MM"))
    )
    (comp (ref "W4")
      (value "J10MM")
      (footprint "eagle-import:10")
      (libsource (lib "eagle-import") (part "J10MM"))
    )
  )
  (nets
    (net (code "1") (name "+3V3") (class "Default")
      (node (ref "C53") (pin "1") (pinfunction "1_1") (pintype "passive"))
      (node (ref "C54") (pin "1") (pinfunction "1_1") (pintype "passive"))
      (node (ref "C55") (pin "1") (pinfunction "1_1") (pintype "passive"))
      (node (ref "C56") (pin "1") (pinfunction "1_1") (pintype "passive"))
      (node (ref "D8") (pin "C") (pinfunction "C_C") (pintype "passive"))
      (node (ref "E14") (pin "2") (pinfunction "R0(1)_2") (pintype "input"))
      (node (ref "E15") (pin "3") (pinfunction "R0(2)_3") (pintype "input"))
      (node (ref "E17") (pin "2") (pinfunction "R0(1)_2") (pintype "input"))
      (node (ref "E18") (pin "3") (pinfunction "R0(2)_3") (pintype "input"))
      (node (ref "E20") (pin "10") (pinfunction "PRE_10") (pintype "input"))
      (node (ref "E20") (pin "2") (pinfunction "D_2") (pintype "input"))
      (node (ref "E20") (pin "4") (pinfunction "PRE_4") (pintype "input"))
      (node (ref "E27") (pin "1") (pinfunction "CLR_1") (pintype "input"))
      (node (ref "E27") (pin "10") (pinfunction "PRE_10") (pintype "input"))
      (node (ref "E28") (pin "16") (pinfunction "16_16") (pintype "passive"))
      (node (ref "E34") (pin "11") (pinfunction "I0_11") (pintype "input"))
      (node (ref "E36") (pin "11") (pinfunction "B2_11") (pintype "input"))
      (node (ref "E36") (pin "2") (pinfunction "B0_2") (pintype "input"))
      (node (ref "E42") (pin "1") (pinfunction "CLR_1") (pintype "input"))
      (node (ref "E42") (pin "10") (pinfunction "PRE_10") (pintype "input"))
      (node (ref "E43") (pin "10") (pinfunction "PRE_10") (pintype "input"))
      (node (ref "E43") (pin "4") (pinfunction "PRE_4") (pintype "input"))
      (node (ref "E56") (pin "1") (pinfunction "CLR_1") (pintype "input"))
      (node (ref "E56") (pin "10") (pinfunction "PRE_10") (pintype "input"))
      (node (ref "E57") (pin "13") (pinfunction "CLR_13") (pintype "input"))
      (node (ref "E8") (pin "2") (pinfunction "R0(1)_2") (pintype "input"))
      (node (ref "E9") (pin "7") (pinfunction "R0(2)_7") (pintype "input"))
      (node (ref "R1") (pin "2") (pinfunction "2_2") (pintype "passive"))
      (node (ref "R10") (pin "2") (pinfunction "2_2") (pintype "passive"))
      (node (ref "R11") (pin "2") (pinfunction "2_2") (pintype "passive"))
      (node (ref "R12") (pin "2") (pinfunction "2_2") (pintype "passive"))
      (node (ref "R15") (pin "2") (pinfunction "2_2") (pintype "passive"))
      (node (ref "R16") (pin "2") (pinfunction "2_2") (pintype "passive"))
      (node (ref "R17") (pin "2") (pinfunction "2_2") (pintype "passive"))
      (node (ref "R2") (pin "2") (pinfunction "2_2") (pintype "passive"))
      (node (ref "R21") (pin "2") (pinfunction "2_2") (pintype "passive"))
      (node (ref "R22") (pin "2") (pinfunction "2_2") (pintype "passive"))
      (node (ref "R23") (pin "2") (pinfunction "2_2") (pintype "passive"))
      (node (ref "R24") (pin "2") (pinfunction "2_2") (pintype "passive"))
      (node (ref "R25") (pin "2") (pinfunction "2_2") (pintype "passive"))
      (node (ref "R28") (pin "2") (pinfunction "2_2") (pintype "passive"))
      (node (ref "R29") (pin "2") (pinfunction "2_2") (pintype "passive"))
      (node (ref "R3") (pin "2") (pinfunction "2_2") (pintype "passive"))
      (node (ref "R30") (pin "2") (pinfunction "2_2") (pintype "passive"))
      (node (ref "R31") (pin "2") (pinfunction "2_2") (pintype "passive"))
      (node (ref "R32") (pin "2") (pinfunction "2_2") (pintype "passive"))
      (node (ref "R35") (pin "2") (pinfunction "2_2") (pintype "passive"))
      (node (ref "R36") (pin "2") (pinfunction "2_2") (pintype "passive"))
      (node (ref "R37") (pin "2") (pinfunction "2_2") (pintype "passive"))
      (node (ref "R4") (pin "2") (pinfunction "2_2") (pintype "passive"))
      (node (ref "R5") (pin "2") (pinfunction "2_2") (pintype "passive"))
      (node (ref "R6") (pin "2") (pinfunction "2_2") (pintype "passive"))
      (node (ref "R7") (pin "2") (pinfunction "2_2") (pintype "passive"))
      (node (ref "R8") (pin "2") (pinfunction "2_2") (pintype "passive"))
      (node (ref "R9") (pin "2") (pinfunction "2_2") (pintype "passive"))
    )
    (net (code "2") (name "+12V") (class "Default")
      (node (ref "D6") (pin "C") (pinfunction "C_C") (pintype "passive"))
      (node (ref "R62") (pin "1") (pinfunction "1_1") (pintype "passive"))
    )
    (net (code "3") (name "+15V") (class "Default")
      (node (ref "C62") (pin "+") (pinfunction "+_+") (pintype "passive"))
      (node (ref "R62") (pin "2") (pinfunction "2_2") (pintype "passive"))
      (node (ref "U$2") (pin "DA2") (pinfunction "1_DA2") (pintype "bidirectional"))
    )
    (net (code "4") (name "-12V") (class "Default")
      (node (ref "C18") (pin "1") (pinfunction "1_1") (pintype "passive"))
      (node (ref "D1") (pin "A") (pinfunction "A_A") (pintype "passive"))
      (node (ref "E19") (pin "2") (pinfunction "VGG_2") (pintype "power_in"))
      (node (ref "R44") (pin "2") (pinfunction "2_2") (pintype "passive"))
    )
    (net (code "5") (name "-15V") (class "Default")
      (node (ref "C63") (pin "-") (pinfunction "-_-") (pintype "passive"))
      (node (ref "D4") (pin "A") (pinfunction "A_A") (pintype "passive"))
      (node (ref "Q1") (pin "1") (pinfunction "E_1") (pintype "passive"))
      (node (ref "R39") (pin "1") (pinfunction "1_1") (pintype "passive"))
      (node (ref "R43") (pin "1") (pinfunction "1_1") (pintype "passive"))
      (node (ref "R44") (pin "1") (pinfunction "1_1") (pintype "passive"))
      (node (ref "R45") (pin "1") (pinfunction "1_1") (pintype "passive"))
      (node (ref "R47") (pin "1") (pinfunction "1_1") (pintype "passive"))
      (node (ref "R59") (pin "1") (pinfunction "1_1") (pintype "passive"))
      (node (ref "U$2") (pin "DB2") (pinfunction "1_DB2") (pintype "bidirectional"))
    )
    (net (code "6") (name "B1") (class "Default")
      (node (ref "E22") (pin "9") (pinfunction "C_9") (pintype "input"))
      (node (ref "E28") (pin "12") (pinfunction "12_12") (pintype "passive"))
      (node (ref "R15") (pin "1") (pinfunction "1_1") (pintype "passive"))
      (node (ref "SP2") (pin "16") (pinfunction "2_16") (pintype "passive"))
    )
    (net (code "7") (name "B2") (class "Default")
      (node (ref "E22") (pin "10") (pinfunction "B_10") (pintype "input"))
      (node (ref "E28") (pin "11") (pinfunction "11_11") (pintype "passive"))
      (node (ref "R16") (pin "1") (pinfunction "1_1") (pintype "passive"))
      (node (ref "SP2") (pin "15") (pinfunction "2_15") (pintype "passive"))
    )
    (net (code "8") (name "B3") (class "Default")
      (node (ref "E22") (pin "11") (pinfunction "A_11") (pintype "input"))
      (node (ref "E28") (pin "14") (pinfunction "14_14") (pintype "passive"))
      (node (ref "R17") (pin "1") (pinfunction "1_1") (pintype "passive"))
      (node (ref "SP1") (pin "16") (pinfunction "2_16") (pintype "passive"))
    )
    (net (code "9") (name "BD96_192") (class "Default")
      (node (ref "E22") (pin "4") (pinfunction "D0_4") (pintype "input"))
      (node (ref "W2") (pin "2") (pinfunction "2_2") (pintype "passive"))
      (node (ref "W5") (pin "2") (pinfunction "2_2") (pintype "passive"))
    )
    (net (code "10") (name "BD110") (class "Default")
      (node (ref "E17") (pin "11") (pinfunction "QD_11") (pintype "output"))
      (node (ref "E22") (pin "12") (pinfunction "D7_12") (pintype "input"))
    )
    (net (code "11") (name "BD150") (class "Default")
      (node (ref "E18") (pin "11") (pinfunction "QD_11") (pintype "output"))
      (node (ref "E21") (pin "10") (pinfunction "I1_10") (pintype "input"))
      (node (ref "E22") (pin "13") (pinfunction "D6_13") (pintype "input"))
    )
    (net (code "12") (name "BD300") (class "Default")
      (node (ref "E18") (pin "8") (pinfunction "QC_8") (pintype "output"))
      (node (ref "E22") (pin "14") (pinfunction "D5_14") (pintype "input"))
    )
    (net (code "13") (name "BD600") (class "Default")
      (node (ref "E18") (pin "9") (pinfunction "QB_9") (pintype "output"))
      (node (ref "E22") (pin "15") (pinfunction "D4_15") (pintype "input"))
    )
    (net (code "14") (name "BD1200") (class "Default")
      (node (ref "E18") (pin "1") (pinfunction "CKB_1") (pintype "input"))
      (node (ref "E18") (pin "12") (pinfunction "QA_12") (pintype "output"))
      (node (ref "E22") (pin "1") (pinfunction "D3_1") (pintype "input"))
    )
    (net (code "15") (name "BD2400") (class "Default")
      (node (ref "E15") (pin "11") (pinfunction "QD_11") (pintype "output"))
      (node (ref "E18") (pin "14") (pinfunction "CKA_14") (pintype "input"))
      (node (ref "E22") (pin "2") (pinfunction "D2_2") (pintype "input"))
    )
    (net (code "16") (name "BD4800") (class "Default")
      (node (ref "E15") (pin "8") (pinfunction "QC_8") (pintype "output"))
      (node (ref "E22") (pin "3") (pinfunction "D1_3") (pintype "input"))
    )
    (net (code "17") (name "BTP3_L") (class "Default")
      (node (ref "E35") (pin "12") (pinfunction "I1_12") (pintype "input"))
      (node (ref "E36") (pin "7") (pinfunction "S1_7") (pintype "input"))
      (node (ref "E37") (pin "8") (pinfunction "I0_8") (pintype "input"))
      (node (ref "E52") (pin "13") (pinfunction "O_13") (pintype "output"))
    )
    (net (code "18") (name "BTX_BUF_EMPTY") (class "Default")
      (node (ref "E40") (pin "12") (pinfunction "I0_12") (pintype "input"))
      (node (ref "E46") (pin "3") (pinfunction "O_3") (pintype "output"))
      (node (ref "E49") (pin "1") (pinfunction "I_1") (pintype "input"))
      (node (ref "E57") (pin "3") (pinfunction "CLK_3") (pintype "input"))
    )
    (net (code "19") (name "B_PAUSE_H") (class "Default")
      (node (ref "E16") (pin "10") (pinfunction "O_10") (pintype "output"))
      (node (ref "E34") (pin "6") (pinfunction "I1_6") (pintype "input"))
      (node (ref "E47") (pin "10") (pinfunction "I1_10") (pintype "input"))
    )
    (net (code "20") (name "B_PAUSE_L") (class "Default")
      (node (ref "E10") (pin "10") (pinfunction "I1_10") (pintype "input"))
      (node (ref "E10") (pin "11") (pinfunction "I0_11") (pintype "input"))
      (node (ref "E10") (pin "5") (pinfunction "I1_5") (pintype "input"))
      (node (ref "E10") (pin "6") (pinfunction "I0_6") (pintype "input"))
      (node (ref "E12") (pin "10") (pinfunction "I1_10") (pintype "input"))
      (node (ref "E12") (pin "11") (pinfunction "I0_11") (pintype "input"))
      (node (ref "E12") (pin "3") (pinfunction "O_3") (pintype "output"))
      (node (ref "E13") (pin "12") (pinfunction "I2_12") (pintype "input"))
      (node (ref "E16") (pin "11") (pinfunction "I_11") (pintype "input"))
      (node (ref "E53") (pin "13") (pinfunction "I3_13") (pintype "input"))
    )
    (net (code "21") (name "C0_L") (class "Default")
      (node (ref "E34") (pin "10") (pinfunction "O_10") (pintype "open_collector"))
      (node (ref "U$2") (pin "CE1") (pinfunction "1_CE1") (pintype "bidirectional"))
    )
    (net (code "22") (name "C1_L") (class "Default")
      (node (ref "E34") (pin "1") (pinfunction "O_1") (pintype "open_collector"))
      (node (ref "E34") (pin "13") (pinfunction "O_13") (pintype "open_collector"))
      (node (ref "U$2") (pin "CH1") (pinfunction "1_CH1") (pintype "bidirectional"))
    )
    (net (code "23") (name "CLKO_EN") (class "Default")
      (node (ref "E28") (pin "5") (pinfunction "5_5") (pintype "passive"))
      (node (ref "E3") (pin "12") (pinfunction "I0_12") (pintype "input"))
      (node (ref "R36") (pin "1") (pinfunction "1_1") (pintype "passive"))
    )
    (net (code "24") (name "COUNT_FILLCHAR") (class "Default")
      (node (ref "E32") (pin "9") (pinfunction "I_9") (pintype "input"))
      (node (ref "E37") (pin "13") (pinfunction "O_13") (pintype "output"))
      (node (ref "E43") (pin "11") (pinfunction "CLK_11") (pintype "input"))
    )
    (net (code "25") (name "DATA00_L") (class "Default")
      (node (ref "E11") (pin "10") (pinfunction "O_10") (pintype "open_collector"))
      (node (ref "U$2") (pin "AR1") (pinfunction "1_AR1") (pintype "bidirectional"))
    )
    (net (code "26") (name "DATA01_L") (class "Default")
      (node (ref "E11") (pin "13") (pinfunction "O_13") (pintype "open_collector"))
      (node (ref "U$2") (pin "AS1") (pinfunction "1_AS1") (pintype "bidirectional"))
    )
    (net (code "27") (name "DATA02_L") (class "Default")
      (node (ref "E11") (pin "4") (pinfunction "O_4") (pintype "open_collector"))
      (node (ref "U$2") (pin "AU1") (pinfunction "1_AU1") (pintype "bidirectional"))
    )
    (net (code "28") (name "DATA03_L") (class "Default")
      (node (ref "E11") (pin "1") (pinfunction "O_1") (pintype "open_collector"))
      (node (ref "U$2") (pin "AV1") (pinfunction "1_AV1") (pintype "bidirectional"))
    )
    (net (code "29") (name "DATA04_L") (class "Default")
      (node (ref "E23") (pin "10") (pinfunction "O_10") (pintype "open_collector"))
      (node (ref "E24") (pin "12") (pinfunction "I1_12") (pintype "input"))
      (node (ref "U$2") (pin "BR1") (pinfunction "1_BR1") (pintype "bidirectional"))
    )
    (net (code "30") (name "DATA05_L") (class "Default")
      (node (ref "E23") (pin "13") (pinfunction "O_13") (pintype "open_collector"))
      (node (ref "E24") (pin "9") (pinfunction "I0_9") (pintype "input"))
      (node (ref "U$2") (pin "BS1") (pinfunction "1_BS1") (pintype "bidirectional"))
    )
    (net (code "31") (name "DATA06_L") (class "Default")
      (node (ref "E23") (pin "4") (pinfunction "O_4") (pintype "open_collector"))
      (node (ref "E24") (pin "7") (pinfunction "I1_7") (pintype "input"))
      (node (ref "U$2") (pin "BU1") (pinfunction "1_BU1") (pintype "bidirectional"))
    )
    (net (code "32") (name "DATA07_L") (class "Default")
      (node (ref "E23") (pin "1") (pinfunction "O_1") (pintype "open_collector"))
      (node (ref "E24") (pin "4") (pinfunction "I0_4") (pintype "input"))
      (node (ref "U$2") (pin "BV1") (pinfunction "1_BV1") (pintype "bidirectional"))
    )
    (net (code "33") (name "DATA08_L") (class "Default")
      (node (ref "E29") (pin "10") (pinfunction "O_10") (pintype "open_collector"))
      (node (ref "E30") (pin "12") (pinfunction "I1_12") (pintype "input"))
      (node (ref "U$2") (pin "DR1") (pinfunction "1_DR1") (pintype "bidirectional"))
    )
    (net (code "34") (name "DATA09_L") (class "Default")
      (node (ref "E29") (pin "13") (pinfunction "O_13") (pintype "open_collector"))
      (node (ref "E30") (pin "9") (pinfunction "I0_9") (pintype "input"))
      (node (ref "U$2") (pin "DS1") (pinfunction "1_DS1") (pintype "bidirectional"))
    )
    (net (code "35") (name "DATA10_L") (class "Default")
      (node (ref "E29") (pin "4") (pinfunction "O_4") (pintype "open_collector"))
      (node (ref "E30") (pin "7") (pinfunction "I1_7") (pintype "input"))
      (node (ref "E55") (pin "4") (pinfunction "I0_4") (pintype "input"))
      (node (ref "U$2") (pin "DU1") (pinfunction "1_DU1") (pintype "bidirectional"))
    )
    (net (code "36") (name "DATA11_L") (class "Default")
      (node (ref "E29") (pin "1") (pinfunction "O_1") (pintype "open_collector"))
      (node (ref "E30") (pin "4") (pinfunction "I0_4") (pintype "input"))
      (node (ref "E55") (pin "7") (pinfunction "I1_7") (pintype "input"))
      (node (ref "U$2") (pin "DV1") (pinfunction "1_DV1") (pintype "bidirectional"))
    )
    (net (code "37") (name "EIA_IN") (class "Default")
      (node (ref "E45") (pin "1") (pinfunction "I_1") (pintype "input"))
      (node (ref "J1") (pin "J") (pinfunction "8_J") (pintype "bidirectional"))
    )
    (net (code "38") (name "EIA_OUT") (class "Default")
      (node (ref "C64") (pin "1") (pinfunction "1_1") (pintype "passive"))
      (node (ref "E50") (pin "3") (pinfunction "O_3") (pintype "output"))
      (node (ref "J1") (pin "F") (pinfunction "6_F") (pintype "bidirectional"))
    )
    (net (code "39") (name "EVN") (class "Default")
      (node (ref "E19") (pin "39") (pinfunction "EPS_39") (pintype "input"))
      (node (ref "E28") (pin "10") (pinfunction "10_10") (pintype "passive"))
      (node (ref "EVN") (pin "2") (pinfunction "2_2") (pintype "passive"))
      (node (ref "R32") (pin "1") (pinfunction "1_1") (pintype "passive"))
    )
    (net (code "40") (name "FILCH_H") (class "Default")
      (node (ref "E37") (pin "12") (pinfunction "I1_12") (pintype "input"))
      (node (ref "E49") (pin "13") (pinfunction "I_13") (pintype "input"))
      (node (ref "E57") (pin "2") (pinfunction "D_2") (pintype "input"))
      (node (ref "E57") (pin "9") (pinfunction "Q_9") (pintype "output"))
    )
    (net (code "41") (name "FILL") (class "Default")
      (node (ref "E28") (pin "3") (pinfunction "3_3") (pintype "passive"))
      (node (ref "E32") (pin "13") (pinfunction "I_13") (pintype "input"))
      (node (ref "FIL") (pin "2") (pinfunction "2_2") (pintype "passive"))
      (node (ref "R22") (pin "1") (pinfunction "1_1") (pintype "passive"))
    )
    (net (code "42") (name "FRAMING_ERR") (class "Default")
      (node (ref "E11") (pin "5") (pinfunction "I0_5") (pintype "input"))
      (node (ref "E13") (pin "2") (pinfunction "I1_2") (pintype "input"))
      (node (ref "E19") (pin "14") (pinfunction "FE_14") (pintype "tri_state"))
    )
    (net (code "43") (name "GND") (class "Default")
      (node (ref "C1") (pin "2") (pinfunction "2_2") (pintype "passive"))
      (node (ref "C10") (pin "2") (pinfunction "2_2") (pintype "passive"))
      (node (ref "C11") (pin "2") (pinfunction "2_2") (pintype "passive"))
      (node (ref "C12") (pin "2") (pinfunction "2_2") (pintype "passive"))
      (node (ref "C13") (pin "2") (pinfunction "2_2") (pintype "passive"))
      (node (ref "C14") (pin "2") (pinfunction "2_2") (pintype "passive"))
      (node (ref "C15") (pin "2") (pinfunction "2_2") (pintype "passive"))
      (node (ref "C16") (pin "2") (pinfunction "2_2") (pintype "passive"))
      (node (ref "C17") (pin "2") (pinfunction "2_2") (pintype "passive"))
      (node (ref "C18") (pin "2") (pinfunction "2_2") (pintype "passive"))
      (node (ref "C19") (pin "2") (pinfunction "2_2") (pintype "passive"))
      (node (ref "C2") (pin "2") (pinfunction "2_2") (pintype "passive"))
      (node (ref "C20") (pin "2") (pinfunction "2_2") (pintype "passive"))
      (node (ref "C21") (pin "2") (pinfunction "2_2") (pintype "passive"))
      (node (ref "C22") (pin "2") (pinfunction "2_2") (pintype "passive"))
      (node (ref "C23") (pin "2") (pinfunction "2_2") (pintype "passive"))
      (node (ref "C24") (pin "2") (pinfunction "2_2") (pintype "passive"))
      (node (ref "C25") (pin "2") (pinfunction "2_2") (pintype "passive"))
      (node (ref "C26") (pin "2") (pinfunction "2_2") (pintype "passive"))
      (node (ref "C27") (pin "2") (pinfunction "2_2") (pintype "passive"))
      (node (ref "C28") (pin "2") (pinfunction "2_2") (pintype "passive"))
      (node (ref "C29") (pin "2") (pinfunction "2_2") (pintype "passive"))
      (node (ref "C3") (pin "2") (pinfunction "2_2") (pintype "passive"))
      (node (ref "C30") (pin "2") (pinfunction "2_2") (pintype "passive"))
      (node (ref "C31") (pin "2") (pinfunction "2_2") (pintype "passive"))
      (node (ref "C32") (pin "2") (pinfunction "2_2") (pintype "passive"))
      (node (ref "C33") (pin "2") (pinfunction "2_2") (pintype "passive"))
      (node (ref "C34") (pin "2") (pinfunction "2_2") (pintype "passive"))
      (node (ref "C35") (pin "2") (pinfunction "2_2") (pintype "passive"))
      (node (ref "C36") (pin "2") (pinfunction "2_2") (pintype "passive"))
      (node (ref "C37") (pin "2") (pinfunction "2_2") (pintype "passive"))
      (node (ref "C38") (pin "2") (pinfunction "2_2") (pintype "passive"))
      (node (ref "C39") (pin "2") (pinfunction "2_2") (pintype "passive"))
      (node (ref "C4") (pin "2") (pinfunction "2_2") (pintype "passive"))
      (node (ref "C40") (pin "2") (pinfunction "2_2") (pintype "passive"))
      (node (ref "C41") (pin "2") (pinfunction "2_2") (pintype "passive"))
      (node (ref "C42") (pin "2") (pinfunction "2_2") (pintype "passive"))
      (node (ref "C43") (pin "2") (pinfunction "2_2") (pintype "passive"))
      (node (ref "C44") (pin "2") (pinfunction "2_2") (pintype "passive"))
      (node (ref "C45") (pin "2") (pinfunction "2_2") (pintype "passive"))
      (node (ref "C46") (pin "2") (pinfunction "2_2") (pintype "passive"))
      (node (ref "C47") (pin "2") (pinfunction "2_2") (pintype "passive"))
      (node (ref "C48") (pin "2") (pinfunction "2_2") (pintype "passive"))
      (node (ref "C49") (pin "2") (pinfunction "2_2") (pintype "passive"))
      (node (ref "C5") (pin "2") (pinfunction "2_2") (pintype "passive"))
      (node (ref "C50") (pin "2") (pinfunction "2_2") (pintype "passive"))
      (node (ref "C51") (pin "2") (pinfunction "2_2") (pintype "passive"))
      (node (ref "C52") (pin "2") (pinfunction "2_2") (pintype "passive"))
      (node (ref "C53") (pin "2") (pinfunction "2_2") (pintype "passive"))
      (node (ref "C54") (pin "2") (pinfunction "2_2") (pintype "passive"))
      (node (ref "C55") (pin "2") (pinfunction "2_2") (pintype "passive"))
      (node (ref "C56") (pin "2") (pinfunction "2_2") (pintype "passive"))
      (node (ref "C57") (pin "2") (pinfunction "2_2") (pintype "passive"))
      (node (ref "C59") (pin "-") (pinfunction "-_-") (pintype "passive"))
      (node (ref "C6") (pin "2") (pinfunction "2_2") (pintype "passive"))
      (node (ref "C60") (pin "-") (pinfunction "-_-") (pintype "passive"))
      (node (ref "C61") (pin "-") (pinfunction "-_-") (pintype "passive"))
      (node (ref "C62") (pin "-") (pinfunction "-_-") (pintype "passive"))
      (node (ref "C63") (pin "+") (pinfunction "+_+") (pintype "passive"))
      (node (ref "C64") (pin "2") (pinfunction "2_2") (pintype "passive"))
      (node (ref "C7") (pin "2") (pinfunction "2_2") (pintype "passive"))
      (node (ref "C8") (pin "2") (pinfunction "2_2") (pintype "passive"))
      (node (ref "C9") (pin "2") (pinfunction "2_2") (pintype "passive"))
      (node (ref "D1") (pin "C") (pinfunction "C_C") (pintype "passive"))
      (node (ref "D6") (pin "A") (pinfunction "A_A") (pintype "passive"))
      (node (ref "E12") (pin "5") (pinfunction "I1_5") (pintype "input"))
      (node (ref "E13") (pin "5") (pinfunction "I3_5") (pintype "input"))
      (node (ref "E19") (pin "16") (pinfunction "/SWE_16") (pintype "input"))
      (node (ref "E19") (pin "3") (pinfunction "GND_3") (pintype "power_in"))
      (node (ref "E19") (pin "4") (pinfunction "/RDE_4") (pintype "input"))
      (node (ref "E22") (pin "7") (pinfunction "G_7") (pintype "input"))
      (node (ref "E27") (pin "2") (pinfunction "D_2") (pintype "input"))
      (node (ref "E36") (pin "14") (pinfunction "B3_14") (pintype "input"))
      (node (ref "E36") (pin "5") (pinfunction "B1_5") (pintype "input"))
      (node (ref "E39") (pin "2") (pinfunction "D_2") (pintype "input"))
      (node (ref "E42") (pin "2") (pinfunction "D_2") (pintype "input"))
      (node (ref "E46") (pin "6") (pinfunction "I0_6") (pintype "input"))
      (node (ref "E50") (pin "4") (pinfunction "I0_4") (pintype "input"))
      (node (ref "E50") (pin "5") (pinfunction "I1_5") (pintype "input"))
      (node (ref "E52") (pin "11") (pinfunction "I0_11") (pintype "input"))
      (node (ref "E55") (pin "10") (pinfunction "I1_10") (pintype "input"))
      (node (ref "E55") (pin "12") (pinfunction "I1_12") (pintype "input"))
      (node (ref "EVN") (pin "1") (pinfunction "1_1") (pintype "passive"))
      (node (ref "FIL") (pin "1") (pinfunction "1_1") (pintype "passive"))
      (node (ref "J1") (pin "A") (pinfunction "1_A") (pintype "bidirectional"))
      (node (ref "J1") (pin "B") (pinfunction "2_B") (pintype "bidirectional"))
      (node (ref "J1") (pin "SS") (pinfunction "37_SS") (pintype "bidirectional"))
      (node (ref "J1") (pin "TT") (pinfunction "38_TT") (pintype "bidirectional"))
      (node (ref "J1") (pin "UU") (pinfunction "39_UU") (pintype "bidirectional"))
      (node (ref "J1") (pin "VV") (pinfunction "40_VV") (pintype "bidirectional"))
      (node (ref "NB1") (pin "1") (pinfunction "1_1") (pintype "passive"))
      (node (ref "NB2") (pin "1") (pinfunction "1_1") (pintype "passive"))
      (node (ref "NP") (pin "1") (pinfunction "1_1") (pintype "passive"))
      (node (ref "R20") (pin "1") (pinfunction "1_1") (pintype "passive"))
      (node (ref "R34") (pin "1") (pinfunction "1_1") (pintype "passive"))
      (node (ref "R35") (pin "1") (pinfunction "1_1") (pintype "passive"))
      (node (ref "SB") (pin "1") (pinfunction "1_1") (pintype "passive"))
      (node (ref "SP1") (pin "1") (pinfunction "1_1") (pintype "passive"))
      (node (ref "SP1") (pin "2") (pinfunction "1_2") (pintype "passive"))
      (node (ref "SP1") (pin "3") (pinfunction "1_3") (pintype "passive"))
      (node (ref "SP1") (pin "4") (pinfunction "1_4") (pintype "passive"))
      (node (ref "SP1") (pin "5") (pinfunction "1_5") (pintype "passive"))
      (node (ref "SP1") (pin "6") (pinfunction "1_6") (pintype "passive"))
      (node (ref "SP1") (pin "7") (pinfunction "1_7") (pintype "passive"))
      (node (ref "SP1") (pin "8") (pinfunction "1_8") (pintype "passive"))
      (node (ref "SP2") (pin "1") (pinfunction "1_1") (pintype "passive"))
      (node (ref "SP2") (pin "2") (pinfunction "1_2") (pintype "passive"))
      (node (ref "SP2") (pin "3") (pinfunction "1_3") (pintype "passive"))
      (node (ref "SP2") (pin "4") (pinfunction "1_4") (pintype "passive"))
      (node (ref "SP2") (pin "5") (pinfunction "1_5") (pintype "passive"))
      (node (ref "SP2") (pin "6") (pinfunction "1_6") (pintype "passive"))
      (node (ref "SP2") (pin "7") (pinfunction "1_7") (pintype "passive"))
      (node (ref "SP2") (pin "8") (pinfunction "1_8") (pintype "passive"))
      (node (ref "SWD") (pin "1") (pinfunction "1_1") (pintype "passive"))
      (node (ref "U$2") (pin "AC1") (pinfunction "1_AC1") (pintype "bidirectional"))
      (node (ref "U$2") (pin "AC2") (pinfunction "1_AC2") (pintype "bidirectional"))
      (node (ref "U$2") (pin "AF1") (pinfunction "1_AF1") (pintype "bidirectional"))
      (node (ref "U$2") (pin "AF2") (pinfunction "1_AF2") (pintype "bidirectional"))
      (node (ref "U$2") (pin "AN1") (pinfunction "1_AN1") (pintype "bidirectional"))
      (node (ref "U$2") (pin "AN2") (pinfunction "1_AN2") (pintype "bidirectional"))
      (node (ref "U$2") (pin "AT1") (pinfunction "1_AT1") (pintype "bidirectional"))
      (node (ref "U$2") (pin "AT2") (pinfunction "1_AT2") (pintype "bidirectional"))
      (node (ref "U$2") (pin "BC1") (pinfunction "1_BC1") (pintype "bidirectional"))
      (node (ref "U$2") (pin "BC2") (pinfunction "1_BC2") (pintype "bidirectional"))
      (node (ref "U$2") (pin "BF1") (pinfunction "1_BF1") (pintype "bidirectional"))
      (node (ref "U$2") (pin "BF2") (pinfunction "1_BF2") (pintype "bidirectional"))
      (node (ref "U$2") (pin "BN1") (pinfunction "1_BN1") (pintype "bidirectional"))
      (node (ref "U$2") (pin "BN2") (pinfunction "1_BN2") (pintype "bidirectional"))
      (node (ref "U$2") (pin "BT1") (pinfunction "1_BT1") (pintype "bidirectional"))
      (node (ref "U$2") (pin "BT2") (pinfunction "1_BT2") (pintype "bidirectional"))
      (node (ref "U$2") (pin "CC1") (pinfunction "1_CC1") (pintype "bidirectional"))
      (node (ref "U$2") (pin "CC2") (pinfunction "1_CC2") (pintype "bidirectional"))
      (node (ref "U$2") (pin "CF1") (pinfunction "1_CF1") (pintype "bidirectional"))
      (node (ref "U$2") (pin "CF2") (pinfunction "1_CF2") (pintype "bidirectional"))
      (node (ref "U$2") (pin "CN1") (pinfunction "1_CN1") (pintype "bidirectional"))
      (node (ref "U$2") (pin "CN2") (pinfunction "1_CN2") (pintype "bidirectional"))
      (node (ref "U$2") (pin "CT1") (pinfunction "1_CT1") (pintype "bidirectional"))
      (node (ref "U$2") (pin "CT2") (pinfunction "1_CT2") (pintype "bidirectional"))
      (node (ref "U$2") (pin "DC1") (pinfunction "1_DC1") (pintype "bidirectional"))
      (node (ref "U$2") (pin "DC2") (pinfunction "1_DC2") (pintype "bidirectional"))
      (node (ref "U$2") (pin "DF1") (pinfunction "1_DF1") (pintype "bidirectional"))
      (node (ref "U$2") (pin "DF2") (pinfunction "1_DF2") (pintype "bidirectional"))
      (node (ref "U$2") (pin "DN1") (pinfunction "1_DN1") (pintype "bidirectional"))
      (node (ref "U$2") (pin "DN2") (pinfunction "1_DN2") (pintype "bidirectional"))
      (node (ref "U$2") (pin "DT1") (pinfunction "1_DT1") (pintype "bidirectional"))
      (node (ref "U$2") (pin "DT2") (pinfunction "1_DT2") (pintype "bidirectional"))
      (node (ref "W3") (pin "1") (pinfunction "1_1") (pintype "passive"))
      (node (ref "W4") (pin "1") (pinfunction "1_1") (pintype "passive"))
      (node (ref "Y1A") (pin "7") (pinfunction "GND_7") (pintype "power_in"))
      (node (ref "Y1B") (pin "4") (pinfunction "GND_4") (pintype "power_in"))
    )
    (net (code "44") (name "HAS_ERROR") (class "Default")
      (node (ref "E11") (pin "8") (pinfunction "I0_8") (pintype "input"))
      (node (ref "E16") (pin "8") (pinfunction "O_8") (pintype "output"))
    )
    (net (code "45") (name "INITIALIZE") (class "Default")
      (node (ref "E46") (pin "7") (pinfunction "I1_7") (pintype "input"))
      (node (ref "U$2") (pin "CR1") (pinfunction "1_CR1") (pintype "bidirectional"))
    )
    (net (code "46") (name "INIT_H") (class "Default")
      (node (ref "E37") (pin "6") (pinfunction "I1_6") (pintype "input"))
      (node (ref "E46") (pin "2") (pinfunction "O_2") (pintype "output"))
      (node (ref "E48") (pin "1") (pinfunction "I0_1") (pintype "input"))
      (node (ref "E48") (pin "2") (pinfunction "I1_2") (pintype "input"))
      (node (ref "E48") (pin "4") (pinfunction "I2_4") (pintype "input"))
      (node (ref "E48") (pin "5") (pinfunction "I3_5") (pintype "input"))
    )
    (net (code "47") (name "INIT_L") (class "Default")
      (node (ref "E36") (pin "9") (pinfunction "S0_9") (pintype "input"))
      (node (ref "E39") (pin "1") (pinfunction "CLR_1") (pintype "input"))
      (node (ref "E43") (pin "1") (pinfunction "CLR_1") (pintype "input"))
      (node (ref "E43") (pin "13") (pinfunction "CLR_13") (pintype "input"))
      (node (ref "E48") (pin "6") (pinfunction "O_6") (pintype "output"))
      (node (ref "E56") (pin "13") (pinfunction "CLR_13") (pintype "input"))
      (node (ref "E56") (pin "4") (pinfunction "PRE_4") (pintype "input"))
      (node (ref "E57") (pin "10") (pinfunction "PRE_10") (pintype "input"))
    )
    (net (code "48") (name "INTERNAL_IO_L") (class "Default")
      (node (ref "E34") (pin "4") (pinfunction "O_4") (pintype "open_collector"))
      (node (ref "U$2") (pin "CL1") (pinfunction "1_CL1") (pintype "bidirectional"))
    )
    (net (code "49") (name "INT_ENAB_H") (class "Default")
      (node (ref "E33") (pin "6") (pinfunction "I1_6") (pintype "input"))
      (node (ref "E56") (pin "5") (pinfunction "Q_5") (pintype "output"))
    )
    (net (code "50") (name "INT_ENAB_L") (class "Default")
      (node (ref "E53") (pin "1") (pinfunction "I0_1") (pintype "input"))
      (node (ref "E53") (pin "2") (pinfunction "I1_2") (pintype "input"))
      (node (ref "E56") (pin "6") (pinfunction "~{Q}_6") (pintype "output"))
    )
    (net (code "51") (name "INT_RQST_L") (class "Default")
      (node (ref "E33") (pin "4") (pinfunction "O_4") (pintype "open_collector"))
      (node (ref "U$2") (pin "CP1") (pinfunction "1_CP1") (pintype "bidirectional"))
    )
    (net (code "52") (name "IO_KCF_L") (class "Default")
      (node (ref "E20") (pin "3") (pinfunction "CLK_3") (pintype "input"))
      (node (ref "E27") (pin "4") (pinfunction "PRE_4") (pintype "input"))
      (node (ref "E36") (pin "4") (pinfunction "F1_4") (pintype "output"))
    )
    (net (code "53") (name "IO_PAUSE_L") (class "Default")
      (node (ref "E12") (pin "4") (pinfunction "I0_4") (pintype "input"))
      (node (ref "U$2") (pin "CD1") (pinfunction "1_CD1") (pintype "bidirectional"))
    )
    (net (code "54") (name "IO_RDRRUN_L") (class "Default")
      (node (ref "E36") (pin "3") (pinfunction "F0_3") (pintype "output"))
      (node (ref "E39") (pin "4") (pinfunction "PRE_4") (pintype "input"))
    )
    (net (code "55") (name "IO_READ_H") (class "Default")
      (node (ref "E13") (pin "8") (pinfunction "O_8") (pintype "output"))
      (node (ref "E16") (pin "5") (pinfunction "I_5") (pintype "input"))
      (node (ref "E23") (pin "11") (pinfunction "I0_11") (pintype "input"))
      (node (ref "E23") (pin "3") (pinfunction "I1_3") (pintype "input"))
      (node (ref "E23") (pin "6") (pinfunction "I1_6") (pintype "input"))
      (node (ref "E23") (pin "8") (pinfunction "I0_8") (pintype "input"))
      (node (ref "E29") (pin "11") (pinfunction "I0_11") (pintype "input"))
      (node (ref "E29") (pin "3") (pinfunction "I1_3") (pintype "input"))
      (node (ref "E29") (pin "6") (pinfunction "I1_6") (pintype "input"))
      (node (ref "E29") (pin "8") (pinfunction "I0_8") (pintype "input"))
      (node (ref "E34") (pin "12") (pinfunction "I1_12") (pintype "input"))
    )
    (net (code "56") (name "IO_TCF_L") (class "Default")
      (node (ref "E36") (pin "13") (pinfunction "F3_13") (pintype "output"))
      (node (ref "E57") (pin "1") (pinfunction "CLR_1") (pintype "input"))
    )
    (net (code "57") (name "IO_TPC_L") (class "Default")
      (node (ref "E32") (pin "5") (pinfunction "I_5") (pintype "input"))
      (node (ref "E36") (pin "12") (pinfunction "F2_12") (pintype "output"))
      (node (ref "E40") (pin "10") (pinfunction "I1_10") (pintype "input"))
    )
    (net (code "58") (name "MD03") (class "Default")
      (node (ref "E12") (pin "12") (pinfunction "I1_12") (pintype "input"))
      (node (ref "U$2") (pin "AP1") (pinfunction "1_AP1") (pintype "bidirectional"))
    )
    (net (code "59") (name "MD04") (class "Default")
      (node (ref "E10") (pin "12") (pinfunction "I1_12") (pintype "input"))
      (node (ref "U$2") (pin "BK1") (pinfunction "1_BK1") (pintype "bidirectional"))
    )
    (net (code "60") (name "MD05") (class "Default")
      (node (ref "E10") (pin "4") (pinfunction "I0_4") (pintype "input"))
      (node (ref "U$2") (pin "BL1") (pinfunction "1_BL1") (pintype "bidirectional"))
    )
    (net (code "61") (name "MD06") (class "Default")
      (node (ref "E10") (pin "7") (pinfunction "I1_7") (pintype "input"))
      (node (ref "U$2") (pin "BM1") (pinfunction "1_BM1") (pintype "bidirectional"))
    )
    (net (code "62") (name "MD07") (class "Default")
      (node (ref "E10") (pin "9") (pinfunction "I0_9") (pintype "input"))
      (node (ref "U$2") (pin "BP1") (pinfunction "1_BP1") (pintype "bidirectional"))
    )
    (net (code "63") (name "MD08") (class "Default")
      (node (ref "E12") (pin "9") (pinfunction "I0_9") (pintype "input"))
      (node (ref "U$2") (pin "DK1") (pinfunction "1_DK1") (pintype "bidirectional"))
    )
    (net (code "64") (name "MD09") (class "Default")
      (node (ref "E52") (pin "9") (pinfunction "I0_9") (pintype "input"))
      (node (ref "U$2") (pin "DL1") (pinfunction "1_DL1") (pintype "bidirectional"))
    )
    (net (code "65") (name "MD10") (class "Default")
      (node (ref "E52") (pin "7") (pinfunction "I1_7") (pintype "input"))
      (node (ref "U$2") (pin "DM1") (pinfunction "1_DM1") (pintype "bidirectional"))
    )
    (net (code "66") (name "MD11") (class "Default")
      (node (ref "E52") (pin "4") (pinfunction "I0_4") (pintype "input"))
      (node (ref "U$2") (pin "DP1") (pinfunction "1_DP1") (pintype "bidirectional"))
    )
    (net (code "67") (name "NB1") (class "Default")
      (node (ref "E19") (pin "38") (pinfunction "NB1_38") (pintype "input"))
      (node (ref "E6") (pin "16") (pinfunction "16_16") (pintype "passive"))
      (node (ref "NB1") (pin "2") (pinfunction "2_2") (pintype "passive"))
      (node (ref "R31") (pin "1") (pinfunction "1_1") (pintype "passive"))
    )
    (net (code "68") (name "NB2") (class "Default")
      (node (ref "E19") (pin "37") (pinfunction "NB2_37") (pintype "input"))
      (node (ref "E6") (pin "15") (pinfunction "15_15") (pintype "passive"))
      (node (ref "NB2") (pin "2") (pinfunction "2_2") (pintype "passive"))
      (node (ref "R30") (pin "1") (pinfunction "1_1") (pintype "passive"))
    )
    (net (code "69") (name "NP") (class "Default")
      (node (ref "E19") (pin "35") (pinfunction "NP_35") (pintype "input"))
      (node (ref "E6") (pin "2") (pinfunction "2_2") (pintype "passive"))
      (node (ref "NP") (pin "2") (pinfunction "2_2") (pintype "passive"))
      (node (ref "R28") (pin "1") (pinfunction "1_1") (pintype "passive"))
    )
    (net (code "70") (name "Net-(C58-Pad+)") (class "Default")
      (node (ref "C58") (pin "+") (pinfunction "+_+") (pintype "passive"))
      (node (ref "TTY") (pin "2") (pinfunction "2_2") (pintype "passive"))
      (node (ref "W1") (pin "2") (pinfunction "2_2") (pintype "passive"))
    )
    (net (code "71") (name "Net-(C58-Pad-)") (class "Default")
      (node (ref "C58") (pin "-") (pinfunction "-_-") (pintype "passive"))
      (node (ref "R50") (pin "1") (pinfunction "1_1") (pintype "passive"))
      (node (ref "R52") (pin "2") (pinfunction "2_2") (pintype "passive"))
    )
    (net (code "72") (name "Net-(D2-PadA)") (class "Default")
      (node (ref "D2") (pin "A") (pinfunction "A_A") (pintype "passive"))
      (node (ref "D3") (pin "C") (pinfunction "C_C") (pintype "passive"))
    )
    (net (code "73") (name "Net-(D7-PadC)") (class "Default")
      (node (ref "D7") (pin "C") (pinfunction "C_C") (pintype "passive"))
      (node (ref "D8") (pin "A") (pinfunction "A_A") (pintype "passive"))
    )
    (net (code "74") (name "Net-(E1A-I1)") (class "Default")
      (node (ref "E1") (pin "2") (pinfunction "I1_2") (pintype "input"))
      (node (ref "R2") (pin "1") (pinfunction "1_1") (pintype "passive"))
      (node (ref "SP2") (pin "10") (pinfunction "2_10") (pintype "passive"))
    )
    (net (code "75") (name "Net-(E1B-I1)") (class "Default")
      (node (ref "E1") (pin "6") (pinfunction "I1_6") (pintype "input"))
      (node (ref "R5") (pin "1") (pinfunction "1_1") (pintype "passive"))
      (node (ref "SP2") (pin "13") (pinfunction "2_13") (pintype "passive"))
    )
    (net (code "76") (name "Net-(E1C-I0)") (class "Default")
      (node (ref "E1") (pin "8") (pinfunction "I0_8") (pintype "input"))
      (node (ref "R4") (pin "1") (pinfunction "1_1") (pintype "passive"))
      (node (ref "SP2") (pin "12") (pinfunction "2_12") (pintype "passive"))
    )
    (net (code "77") (name "Net-(E1D-I0)") (class "Default")
      (node (ref "E1") (pin "12") (pinfunction "I0_12") (pintype "input"))
      (node (ref "R3") (pin "1") (pinfunction "1_1") (pintype "passive"))
      (node (ref "SP2") (pin "11") (pinfunction "2_11") (pintype "passive"))
    )
    (net (code "78") (name "Net-(E2A-I1)") (class "Default")
      (node (ref "E2") (pin "2") (pinfunction "I1_2") (pintype "input"))
      (node (ref "R7") (pin "1") (pinfunction "1_1") (pintype "passive"))
      (node (ref "SP1") (pin "9") (pinfunction "2_9") (pintype "passive"))
    )
    (net (code "79") (name "Net-(E2B-I1)") (class "Default")
      (node (ref "E2") (pin "6") (pinfunction "I1_6") (pintype "input"))
      (node (ref "R12") (pin "1") (pinfunction "1_1") (pintype "passive"))
      (node (ref "SP1") (pin "14") (pinfunction "2_14") (pintype "passive"))
    )
    (net (code "80") (name "Net-(E2C-I0)") (class "Default")
      (node (ref "E2") (pin "8") (pinfunction "I0_8") (pintype "input"))
      (node (ref "R6") (pin "1") (pinfunction "1_1") (pintype "passive"))
      (node (ref "SP2") (pin "14") (pinfunction "2_14") (pintype "passive"))
    )
    (net (code "81") (name "Net-(E2D-I0)") (class "Default")
      (node (ref "E2") (pin "12") (pinfunction "I0_12") (pintype "input"))
      (node (ref "R1") (pin "1") (pinfunction "1_1") (pintype "passive"))
      (node (ref "SP2") (pin "9") (pinfunction "2_9") (pintype "passive"))
    )
    (net (code "82") (name "Net-(E3A-O)") (class "Default")
      (node (ref "E3") (pin "3") (pinfunction "O_3") (pintype "output"))
      (node (ref "E3") (pin "4") (pinfunction "I0_4") (pintype "input"))
      (node (ref "E3") (pin "5") (pinfunction "I1_5") (pintype "input"))
      (node (ref "E7") (pin "10") (pinfunction "I1_10") (pintype "input"))
      (node (ref "E7") (pin "5") (pinfunction "I1_5") (pintype "input"))
    )
    (net (code "83") (name "Net-(E3D-I1)") (class "Default")
      (node (ref "E3") (pin "13") (pinfunction "I1_13") (pintype "input"))
      (node (ref "Y1A") (pin "8") (pinfunction "OUT_8") (pintype "output"))
      (node (ref "Y1B") (pin "5") (pinfunction "OUT_5") (pintype "output"))
    )
    (net (code "84") (name "Net-(E5A-I1)") (class "Default")
      (node (ref "E5") (pin "2") (pinfunction "I1_2") (pintype "input"))
      (node (ref "R8") (pin "1") (pinfunction "1_1") (pintype "passive"))
      (node (ref "SP1") (pin "10") (pinfunction "2_10") (pintype "passive"))
    )
    (net (code "85") (name "Net-(E5B-I1)") (class "Default")
      (node (ref "E5") (pin "6") (pinfunction "I1_6") (pintype "input"))
      (node (ref "R11") (pin "1") (pinfunction "1_1") (pintype "passive"))
      (node (ref "SP1") (pin "13") (pinfunction "2_13") (pintype "passive"))
    )
    (net (code "86") (name "Net-(E5C-I0)") (class "Default")
      (node (ref "E5") (pin "8") (pinfunction "I0_8") (pintype "input"))
      (node (ref "R10") (pin "1") (pinfunction "1_1") (pintype "passive"))
      (node (ref "SP1") (pin "12") (pinfunction "2_12") (pintype "passive"))
    )
    (net (code "87") (name "Net-(E5D-I0)") (class "Default")
      (node (ref "E5") (pin "12") (pinfunction "I0_12") (pintype "input"))
      (node (ref "R9") (pin "1") (pinfunction "1_1") (pintype "passive"))
      (node (ref "SP1") (pin "11") (pinfunction "2_11") (pintype "passive"))
    )
    (net (code "88") (name "Net-(E7A-I1)") (class "Default")
      (node (ref "E7") (pin "2") (pinfunction "I1_2") (pintype "input"))
      (node (ref "E7") (pin "4") (pinfunction "I0_4") (pintype "input"))
      (node (ref "E9") (pin "8") (pinfunction "QD_8") (pintype "output"))
    )
    (net (code "89") (name "Net-(E7B-O)") (class "Default")
      (node (ref "E7") (pin "6") (pinfunction "O_6") (pintype "output"))
      (node (ref "E9") (pin "14") (pinfunction "CKA_14") (pintype "input"))
    )
    (net (code "90") (name "Net-(E7C-O)") (class "Default")
      (node (ref "E7") (pin "8") (pinfunction "O_8") (pintype "output"))
      (node (ref "E8") (pin "14") (pinfunction "CKA_14") (pintype "input"))
    )
    (net (code "91") (name "Net-(E8A-CKB)") (class "Default")
      (node (ref "E8") (pin "1") (pinfunction "CKB_1") (pintype "input"))
      (node (ref "E8") (pin "12") (pinfunction "QA_12") (pintype "output"))
    )
    (net (code "92") (name "Net-(E9A-CKB)") (class "Default")
      (node (ref "E9") (pin "1") (pinfunction "CKB_1") (pintype "input"))
      (node (ref "E9") (pin "12") (pinfunction "QA_12") (pintype "output"))
    )
    (net (code "93") (name "Net-(E10A-O)") (class "Default")
      (node (ref "E1") (pin "9") (pinfunction "I1_9") (pintype "input"))
      (node (ref "E10") (pin "3") (pinfunction "O_3") (pintype "output"))
      (node (ref "E5") (pin "9") (pinfunction "I1_9") (pintype "input"))
    )
    (net (code "94") (name "Net-(E10B-O)") (class "Default")
      (node (ref "E1") (pin "13") (pinfunction "I1_13") (pintype "input"))
      (node (ref "E10") (pin "2") (pinfunction "O_2") (pintype "output"))
      (node (ref "E5") (pin "13") (pinfunction "I1_13") (pintype "input"))
    )
    (net (code "95") (name "Net-(E10C-O)") (class "Default")
      (node (ref "E1") (pin "1") (pinfunction "I0_1") (pintype "input"))
      (node (ref "E10") (pin "14") (pinfunction "O_14") (pintype "output"))
      (node (ref "E5") (pin "1") (pinfunction "I0_1") (pintype "input"))
    )
    (net (code "96") (name "Net-(E10D-O)") (class "Default")
      (node (ref "E1") (pin "5") (pinfunction "I0_5") (pintype "input"))
      (node (ref "E10") (pin "13") (pinfunction "O_13") (pintype "output"))
      (node (ref "E5") (pin "5") (pinfunction "I0_5") (pintype "input"))
    )
    (net (code "97") (name "Net-(E11A-I1)") (class "Default")
      (node (ref "E11") (pin "12") (pinfunction "I1_12") (pintype "input"))
      (node (ref "E11") (pin "3") (pinfunction "I1_3") (pintype "input"))
      (node (ref "E11") (pin "6") (pinfunction "I1_6") (pintype "input"))
      (node (ref "E11") (pin "9") (pinfunction "I1_9") (pintype "input"))
      (node (ref "E53") (pin "8") (pinfunction "O_8") (pintype "output"))
    )
    (net (code "98") (name "Net-(E12B-I0)") (class "Default")
      (node (ref "E12") (pin "6") (pinfunction "I0_6") (pintype "input"))
      (node (ref "E2") (pin "3") (pinfunction "O_3") (pintype "open_collector"))
      (node (ref "E2") (pin "4") (pinfunction "O_4") (pintype "open_collector"))
      (node (ref "E41") (pin "13") (pinfunction "C_13") (pintype "input"))
      (node (ref "E5") (pin "10") (pinfunction "O_10") (pintype "open_collector"))
      (node (ref "E5") (pin "11") (pinfunction "O_11") (pintype "open_collector"))
      (node (ref "E5") (pin "3") (pinfunction "O_3") (pintype "open_collector"))
      (node (ref "E5") (pin "4") (pinfunction "O_4") (pintype "open_collector"))
      (node (ref "R60") (pin "1") (pinfunction "1_1") (pintype "passive"))
    )
    (net (code "99") (name "Net-(E12B-I1)") (class "Default")
      (node (ref "E1") (pin "10") (pinfunction "O_10") (pintype "open_collector"))
      (node (ref "E1") (pin "11") (pinfunction "O_11") (pintype "open_collector"))
      (node (ref "E1") (pin "3") (pinfunction "O_3") (pintype "open_collector"))
      (node (ref "E1") (pin "4") (pinfunction "O_4") (pintype "open_collector"))
      (node (ref "E12") (pin "7") (pinfunction "I1_7") (pintype "input"))
      (node (ref "E2") (pin "10") (pinfunction "O_10") (pintype "open_collector"))
      (node (ref "E2") (pin "11") (pinfunction "O_11") (pintype "open_collector"))
      (node (ref "R61") (pin "1") (pinfunction "1_1") (pintype "passive"))
    )
    (net (code "100") (name "Net-(E12C-O)") (class "Default")
      (node (ref "E12") (pin "14") (pinfunction "O_14") (pintype "output"))
      (node (ref "E2") (pin "1") (pinfunction "I0_1") (pintype "input"))
      (node (ref "E2") (pin "13") (pinfunction "I1_13") (pintype "input"))
    )
    (net (code "101") (name "Net-(E12D-O)") (class "Default")
      (node (ref "E12") (pin "13") (pinfunction "O_13") (pintype "output"))
      (node (ref "E2") (pin "5") (pinfunction "I0_5") (pintype "input"))
      (node (ref "E2") (pin "9") (pinfunction "I1_9") (pintype "input"))
    )
    (net (code "102") (name "Net-(E13A-O)") (class "Default")
      (node (ref "E13") (pin "6") (pinfunction "O_6") (pintype "output"))
      (node (ref "E16") (pin "9") (pinfunction "I_9") (pintype "input"))
    )
    (net (code "103") (name "Net-(E13B-I0)") (class "Default")
      (node (ref "E13") (pin "10") (pinfunction "I1_10") (pintype "input"))
      (node (ref "E13") (pin "9") (pinfunction "I0_9") (pintype "input"))
      (node (ref "E16") (pin "2") (pinfunction "O_2") (pintype "output"))
      (node (ref "E35") (pin "9") (pinfunction "I1_9") (pintype "input"))
    )
    (net (code "104") (name "Net-(E14A-CKA)") (class "Default")
      (node (ref "E14") (pin "14") (pinfunction "CKA_14") (pintype "input"))
      (node (ref "E7") (pin "11") (pinfunction "O_11") (pintype "output"))
    )
    (net (code "105") (name "Net-(E14A-CKB)") (class "Default")
      (node (ref "E14") (pin "1") (pinfunction "CKB_1") (pintype "input"))
      (node (ref "E14") (pin "12") (pinfunction "QA_12") (pintype "output"))
    )
    (net (code "106") (name "Net-(E14A-QD)") (class "Default")
      (node (ref "E14") (pin "11") (pinfunction "QD_11") (pintype "output"))
      (node (ref "E17") (pin "14") (pinfunction "CKA_14") (pintype "input"))
      (node (ref "E7") (pin "12") (pinfunction "I0_12") (pintype "input"))
    )
    (net (code "107") (name "Net-(E15A-CKA)") (class "Default")
      (node (ref "E15") (pin "14") (pinfunction "CKA_14") (pintype "input"))
      (node (ref "E7") (pin "3") (pinfunction "O_3") (pintype "output"))
    )
    (net (code "108") (name "Net-(E15A-CKB)") (class "Default")
      (node (ref "E15") (pin "1") (pinfunction "CKB_1") (pintype "input"))
      (node (ref "E15") (pin "12") (pinfunction "QA_12") (pintype "output"))
      (node (ref "W5") (pin "1") (pinfunction "1_1") (pintype "passive"))
    )
    (net (code "109") (name "Net-(E15A-QB)") (class "Default")
      (node (ref "E15") (pin "9") (pinfunction "QB_9") (pintype "output"))
      (node (ref "E7") (pin "1") (pinfunction "I0_1") (pintype "input"))
      (node (ref "W2") (pin "1") (pinfunction "1_1") (pintype "passive"))
    )
    (net (code "110") (name "Net-(E16A-I)") (class "Default")
      (node (ref "E16") (pin "1") (pinfunction "I_1") (pintype "input"))
      (node (ref "E46") (pin "12") (pinfunction "I1_12") (pintype "input"))
      (node (ref "E52") (pin "14") (pinfunction "O_14") (pintype "output"))
    )
    (net (code "111") (name "Net-(E16B-O)") (class "Default")
      (node (ref "E16") (pin "4") (pinfunction "O_4") (pintype "output"))
      (node (ref "E20") (pin "11") (pinfunction "CLK_11") (pintype "input"))
    )
    (net (code "112") (name "Net-(E16C-O)") (class "Default")
      (node (ref "E16") (pin "6") (pinfunction "O_6") (pintype "output"))
      (node (ref "E53") (pin "12") (pinfunction "I2_12") (pintype "input"))
    )
    (net (code "113") (name "Net-(E16F-O)") (class "Default")
      (node (ref "E16") (pin "12") (pinfunction "O_12") (pintype "output"))
      (node (ref "E21") (pin "9") (pinfunction "I0_9") (pintype "input"))
    )
    (net (code "114") (name "Net-(E17A-CKB)") (class "Default")
      (node (ref "E17") (pin "1") (pinfunction "CKB_1") (pintype "input"))
      (node (ref "E17") (pin "12") (pinfunction "QA_12") (pintype "output"))
    )
    (net (code "115") (name "Net-(E19A-CS)") (class "Default")
      (node (ref "E19") (pin "34") (pinfunction "CS_34") (pintype "input"))
      (node (ref "R27") (pin "2") (pinfunction "2_2") (pintype "passive"))
    )
    (net (code "116") (name "Net-(E19A-DB1)") (class "Default")
      (node (ref "E19") (pin "26") (pinfunction "DB1_26") (pintype "input"))
      (node (ref "E31") (pin "2") (pinfunction "Q1_2") (pintype "output"))
    )
    (net (code "117") (name "Net-(E19A-DB2)") (class "Default")
      (node (ref "E19") (pin "27") (pinfunction "DB2_27") (pintype "input"))
      (node (ref "E26") (pin "12") (pinfunction "I7_12") (pintype "input"))
      (node (ref "E31") (pin "7") (pinfunction "Q2_7") (pintype "output"))
    )
    (net (code "118") (name "Net-(E19A-DB3)") (class "Default")
      (node (ref "E19") (pin "28") (pinfunction "DB3_28") (pintype "input"))
      (node (ref "E31") (pin "15") (pinfunction "Q4_15") (pintype "output"))
    )
    (net (code "119") (name "Net-(E19A-DB4)") (class "Default")
      (node (ref "E19") (pin "29") (pinfunction "DB4_29") (pintype "input"))
      (node (ref "E26") (pin "1") (pinfunction "I0_1") (pintype "input"))
      (node (ref "E31") (pin "10") (pinfunction "Q3_10") (pintype "output"))
    )
    (net (code "120") (name "Net-(E19A-DB5)") (class "Default")
      (node (ref "E19") (pin "30") (pinfunction "DB5_30") (pintype "input"))
      (node (ref "E25") (pin "2") (pinfunction "Q1_2") (pintype "output"))
    )
    (net (code "121") (name "Net-(E19A-DB6)") (class "Default")
      (node (ref "E19") (pin "31") (pinfunction "DB6_31") (pintype "input"))
      (node (ref "E25") (pin "7") (pinfunction "Q2_7") (pintype "output"))
    )
    (net (code "122") (name "Net-(E19A-DB7)") (class "Default")
      (node (ref "E19") (pin "32") (pinfunction "DB7_32") (pintype "input"))
      (node (ref "E25") (pin "15") (pinfunction "Q4_15") (pintype "output"))
    )
    (net (code "123") (name "Net-(E19A-DB8)") (class "Default")
      (node (ref "E19") (pin "33") (pinfunction "DB8_33") (pintype "input"))
      (node (ref "E25") (pin "10") (pinfunction "Q3_10") (pintype "output"))
    )
    (net (code "124") (name "Net-(E19A-XR)") (class "Default")
      (node (ref "E19") (pin "21") (pinfunction "XR_21") (pintype "input"))
      (node (ref "E55") (pin "14") (pinfunction "O_14") (pintype "output"))
    )
    (net (code "125") (name "Net-(E20A-CLR)") (class "Default")
      (node (ref "E20") (pin "1") (pinfunction "CLR_1") (pintype "input"))
      (node (ref "E21") (pin "6") (pinfunction "O_6") (pintype "output"))
    )
    (net (code "126") (name "Net-(E20A-Q)") (class "Default")
      (node (ref "E20") (pin "12") (pinfunction "D_12") (pintype "input"))
      (node (ref "E20") (pin "13") (pinfunction "CLR_13") (pintype "input"))
      (node (ref "E20") (pin "5") (pinfunction "Q_5") (pintype "output"))
    )
    (net (code "127") (name "Net-(E20B-Q)") (class "Default")
      (node (ref "E20") (pin "9") (pinfunction "Q_9") (pintype "output"))
      (node (ref "E21") (pin "5") (pinfunction "I1_5") (pintype "input"))
    )
    (net (code "128") (name "Net-(E21A-I0)") (class "Default")
      (node (ref "E21") (pin "1") (pinfunction "I0_1") (pintype "input"))
      (node (ref "E21") (pin "11") (pinfunction "O_11") (pintype "output"))
    )
    (net (code "129") (name "Net-(E21A-I1)") (class "Default")
      (node (ref "E21") (pin "2") (pinfunction "I1_2") (pintype "input"))
      (node (ref "E21") (pin "8") (pinfunction "O_8") (pintype "output"))
    )
    (net (code "130") (name "Net-(E24A-O)") (class "Default")
      (node (ref "E24") (pin "3") (pinfunction "O_3") (pintype "output"))
      (node (ref "E25") (pin "4") (pinfunction "D1_4") (pintype "input"))
    )
    (net (code "131") (name "Net-(E24B-O)") (class "Default")
      (node (ref "E24") (pin "2") (pinfunction "O_2") (pintype "output"))
      (node (ref "E25") (pin "5") (pinfunction "D2_5") (pintype "input"))
    )
    (net (code "132") (name "Net-(E24C-O)") (class "Default")
      (node (ref "E24") (pin "14") (pinfunction "O_14") (pintype "output"))
      (node (ref "E25") (pin "13") (pinfunction "D4_13") (pintype "input"))
    )
    (net (code "133") (name "Net-(E24D-O)") (class "Default")
      (node (ref "E24") (pin "13") (pinfunction "O_13") (pintype "output"))
      (node (ref "E25") (pin "12") (pinfunction "D3_12") (pintype "input"))
    )
    (net (code "134") (name "Net-(E25A-CLK)") (class "Default")
      (node (ref "E25") (pin "9") (pinfunction "CLK_9") (pintype "input"))
      (node (ref "E31") (pin "9") (pinfunction "CLK_9") (pintype "input"))
      (node (ref "E32") (pin "8") (pinfunction "O_8") (pintype "output"))
    )
    (net (code "135") (name "Net-(E25A-CLR)") (class "Default")
      (node (ref "E25") (pin "1") (pinfunction "CLR_1") (pintype "input"))
      (node (ref "E31") (pin "1") (pinfunction "CLR_1") (pintype "input"))
      (node (ref "E32") (pin "6") (pinfunction "O_6") (pintype "output"))
    )
    (net (code "136") (name "Net-(E25A-~{Q1})") (class "Default")
      (node (ref "E25") (pin "3") (pinfunction "~{Q1}_3") (pintype "output"))
      (node (ref "E26") (pin "5") (pinfunction "I4_5") (pintype "input"))
    )
    (net (code "137") (name "Net-(E25A-~{Q2})") (class "Default")
      (node (ref "E25") (pin "6") (pinfunction "~{Q2}_6") (pintype "output"))
      (node (ref "E26") (pin "6") (pinfunction "I5_6") (pintype "input"))
    )
    (net (code "138") (name "Net-(E25A-~{Q4})") (class "Default")
      (node (ref "E25") (pin "14") (pinfunction "~{Q4}_14") (pintype "output"))
      (node (ref "E26") (pin "11") (pinfunction "I6_11") (pintype "input"))
    )
    (net (code "139") (name "Net-(E26A-I1)") (class "Default")
      (node (ref "E26") (pin "2") (pinfunction "I1_2") (pintype "input"))
      (node (ref "E31") (pin "14") (pinfunction "~{Q4}_14") (pintype "output"))
    )
    (net (code "140") (name "Net-(E26A-I2)") (class "Default")
      (node (ref "E26") (pin "3") (pinfunction "I2_3") (pintype "input"))
      (node (ref "E32") (pin "12") (pinfunction "O_12") (pintype "output"))
    )
    (net (code "141") (name "Net-(E26A-I3)") (class "Default")
      (node (ref "E26") (pin "4") (pinfunction "I3_4") (pintype "input"))
      (node (ref "E31") (pin "3") (pinfunction "~{Q1}_3") (pintype "output"))
    )
    (net (code "142") (name "Net-(E27A-CLK)") (class "Default")
      (node (ref "E27") (pin "3") (pinfunction "CLK_3") (pintype "input"))
      (node (ref "E46") (pin "14") (pinfunction "O_14") (pintype "output"))
    )
    (net (code "143") (name "Net-(E27B-CLK)") (class "Default")
      (node (ref "E27") (pin "11") (pinfunction "CLK_11") (pintype "input"))
      (node (ref "E3") (pin "6") (pinfunction "O_6") (pintype "output"))
    )
    (net (code "144") (name "Net-(E30A-O)") (class "Default")
      (node (ref "E30") (pin "3") (pinfunction "O_3") (pintype "output"))
      (node (ref "E31") (pin "4") (pinfunction "D1_4") (pintype "input"))
    )
    (net (code "145") (name "Net-(E30B-O)") (class "Default")
      (node (ref "E30") (pin "2") (pinfunction "O_2") (pintype "output"))
      (node (ref "E31") (pin "5") (pinfunction "D2_5") (pintype "input"))
    )
    (net (code "146") (name "Net-(E30C-O)") (class "Default")
      (node (ref "E30") (pin "14") (pinfunction "O_14") (pintype "output"))
      (node (ref "E31") (pin "13") (pinfunction "D4_13") (pintype "input"))
    )
    (net (code "147") (name "Net-(E30D-O)") (class "Default")
      (node (ref "E30") (pin "13") (pinfunction "O_13") (pintype "output"))
      (node (ref "E31") (pin "12") (pinfunction "D3_12") (pintype "input"))
    )
    (net (code "148") (name "Net-(E32A-O)") (class "Default")
      (node (ref "E32") (pin "2") (pinfunction "O_2") (pintype "output"))
      (node (ref "E33") (pin "3") (pinfunction "I1_3") (pintype "input"))
    )
    (net (code "149") (name "Net-(E32B-I)") (class "Default")
      (node (ref "E32") (pin "3") (pinfunction "I_3") (pintype "input"))
      (node (ref "E40") (pin "5") (pinfunction "I1_5") (pintype "input"))
      (node (ref "E46") (pin "11") (pinfunction "I0_11") (pintype "input"))
      (node (ref "E52") (pin "2") (pinfunction "O_2") (pintype "output"))
    )
    (net (code "150") (name "Net-(E32B-O)") (class "Default")
      (node (ref "E32") (pin "4") (pinfunction "O_4") (pintype "output"))
      (node (ref "E35") (pin "2") (pinfunction "I0_2") (pintype "input"))
      (node (ref "E35") (pin "5") (pinfunction "I0_5") (pintype "input"))
    )
    (net (code "151") (name "Net-(E32E-O)") (class "Default")
      (node (ref "E32") (pin "10") (pinfunction "O_10") (pintype "output"))
      (node (ref "E33") (pin "11") (pinfunction "I0_11") (pintype "input"))
    )
    (net (code "152") (name "Net-(E33B-I0)") (class "Default")
      (node (ref "E33") (pin "5") (pinfunction "I0_5") (pintype "input"))
      (node (ref "E33") (pin "9") (pinfunction "I1_9") (pintype "input"))
      (node (ref "E38") (pin "11") (pinfunction "O_11") (pintype "output"))
    )
    (net (code "153") (name "Net-(E33C-I0)") (class "Default")
      (node (ref "E33") (pin "8") (pinfunction "I0_8") (pintype "input"))
      (node (ref "E53") (pin "6") (pinfunction "O_6") (pintype "output"))
    )
    (net (code "154") (name "Net-(E34A-I0)") (class "Default")
      (node (ref "E34") (pin "2") (pinfunction "I0_2") (pintype "input"))
      (node (ref "E34") (pin "3") (pinfunction "I1_3") (pintype "input"))
      (node (ref "E34") (pin "8") (pinfunction "I0_8") (pintype "input"))
      (node (ref "E34") (pin "9") (pinfunction "I1_9") (pintype "input"))
      (node (ref "E35") (pin "1") (pinfunction "O_1") (pintype "output"))
      (node (ref "E36") (pin "1") (pinfunction "A0_1") (pintype "input"))
      (node (ref "E49") (pin "9") (pinfunction "I_9") (pintype "input"))
    )
    (net (code "155") (name "Net-(E35B-O)") (class "Default")
      (node (ref "E35") (pin "4") (pinfunction "O_4") (pintype "output"))
      (node (ref "E36") (pin "15") (pinfunction "A3_15") (pintype "input"))
    )
    (net (code "156") (name "Net-(E35C-O)") (class "Default")
      (node (ref "E35") (pin "10") (pinfunction "O_10") (pintype "output"))
      (node (ref "E36") (pin "10") (pinfunction "A2_10") (pintype "input"))
    )
    (net (code "157") (name "Net-(E35D-O)") (class "Default")
      (node (ref "E35") (pin "13") (pinfunction "O_13") (pintype "output"))
      (node (ref "E56") (pin "11") (pinfunction "CLK_11") (pintype "input"))
      (node (ref "E56") (pin "3") (pinfunction "CLK_3") (pintype "input"))
    )
    (net (code "158") (name "Net-(E36A-A1)") (class "Default")
      (node (ref "E36") (pin "6") (pinfunction "A1_6") (pintype "input"))
      (node (ref "E40") (pin "3") (pinfunction "O_3") (pintype "output"))
    )
    (net (code "159") (name "Net-(E37A-I0)") (class "Default")
      (node (ref "E37") (pin "2") (pinfunction "I0_2") (pintype "input"))
      (node (ref "E42") (pin "11") (pinfunction "CLK_11") (pintype "input"))
      (node (ref "E8") (pin "8") (pinfunction "QC_8") (pintype "output"))
    )
    (net (code "160") (name "Net-(E37A-I1)") (class "Default")
      (node (ref "E37") (pin "3") (pinfunction "I1_3") (pintype "input"))
      (node (ref "E42") (pin "8") (pinfunction "~{Q}_8") (pintype "output"))
    )
    (net (code "161") (name "Net-(E37A-O)") (class "Default")
      (node (ref "E37") (pin "1") (pinfunction "O_1") (pintype "output"))
      (node (ref "E37") (pin "5") (pinfunction "I0_5") (pintype "input"))
    )
    (net (code "162") (name "Net-(E37B-O)") (class "Default")
      (node (ref "E37") (pin "4") (pinfunction "O_4") (pintype "output"))
      (node (ref "E42") (pin "4") (pinfunction "PRE_4") (pintype "input"))
    )
    (net (code "163") (name "Net-(E37C-O)") (class "Default")
      (node (ref "E37") (pin "10") (pinfunction "O_10") (pintype "output"))
      (node (ref "E49") (pin "5") (pinfunction "I_5") (pintype "input"))
    )
    (net (code "164") (name "Net-(E37D-I0)") (class "Default")
      (node (ref "E37") (pin "11") (pinfunction "I0_11") (pintype "input"))
      (node (ref "E42") (pin "5") (pinfunction "Q_5") (pintype "output"))
    )
    (net (code "165") (name "Net-(E39A-CLK)") (class "Default")
      (node (ref "E39") (pin "3") (pinfunction "CLK_3") (pintype "input"))
      (node (ref "E44") (pin "11") (pinfunction "QD_11") (pintype "output"))
    )
    (net (code "166") (name "Net-(E39A-Q)") (class "Default")
      (node (ref "E39") (pin "5") (pinfunction "Q_5") (pintype "output"))
      (node (ref "E54") (pin "2") (pinfunction "I1_2") (pintype "input"))
    )
    (net (code "167") (name "Net-(E39A-~{Q})") (class "Default")
      (node (ref "E39") (pin "6") (pinfunction "~{Q}_6") (pintype "output"))
      (node (ref "R18") (pin "1") (pinfunction "1_1") (pintype "passive"))
    )
    (net (code "168") (name "Net-(E40A-I1)") (class "Default")
      (node (ref "E40") (pin "2") (pinfunction "I1_2") (pintype "input"))
      (node (ref "E49") (pin "8") (pinfunction "O_8") (pintype "output"))
    )
    (net (code "169") (name "Net-(E40B-I0)") (class "Default")
      (node (ref "E40") (pin "4") (pinfunction "I0_4") (pintype "input"))
      (node (ref "E41") (pin "15") (pinfunction "A_15") (pintype "input"))
      (node (ref "E52") (pin "3") (pinfunction "O_3") (pintype "output"))
    )
    (net (code "170") (name "Net-(E40B-O)") (class "Default")
      (node (ref "E40") (pin "6") (pinfunction "O_6") (pintype "output"))
      (node (ref "E47") (pin "9") (pinfunction "I0_9") (pintype "input"))
    )
    (net (code "171") (name "Net-(E40C-I0)") (class "Default")
      (node (ref "E40") (pin "11") (pinfunction "O_11") (pintype "output"))
      (node (ref "E40") (pin "9") (pinfunction "I0_9") (pintype "input"))
    )
    (net (code "172") (name "Net-(E40C-O)") (class "Default")
      (node (ref "E40") (pin "8") (pinfunction "O_8") (pintype "output"))
      (node (ref "E42") (pin "3") (pinfunction "CLK_3") (pintype "input"))
    )
    (net (code "173") (name "Net-(E40D-I1)") (class "Default")
      (node (ref "E40") (pin "13") (pinfunction "I1_13") (pintype "input"))
      (node (ref "E48") (pin "13") (pinfunction "I3_13") (pintype "input"))
      (node (ref "E49") (pin "12") (pinfunction "O_12") (pintype "output"))
    )
    (net (code "174") (name "Net-(E41A-B)") (class "Default")
      (node (ref "E41") (pin "14") (pinfunction "B_14") (pintype "input"))
      (node (ref "E46") (pin "13") (pinfunction "O_13") (pintype "output"))
    )
    (net (code "175") (name "Net-(E41A-D)") (class "Default")
      (node (ref "E41") (pin "12") (pinfunction "D_12") (pintype "input"))
      (node (ref "E47") (pin "8") (pinfunction "O_8") (pintype "output"))
    )
    (net (code "176") (name "Net-(E42A-~{Q})") (class "Default")
      (node (ref "E42") (pin "12") (pinfunction "D_12") (pintype "input"))
      (node (ref "E42") (pin "13") (pinfunction "CLR_13") (pintype "input"))
      (node (ref "E42") (pin "6") (pinfunction "~{Q}_6") (pintype "output"))
    )
    (net (code "177") (name "Net-(E42B-Q)") (class "Default")
      (node (ref "E42") (pin "9") (pinfunction "Q_9") (pintype "output"))
      (node (ref "E54") (pin "12") (pinfunction "I0_12") (pintype "input"))
    )
    (net (code "178") (name "Net-(E43A-CLK)") (class "Default")
      (node (ref "E43") (pin "12") (pinfunction "D_12") (pintype "input"))
      (node (ref "E43") (pin "3") (pinfunction "CLK_3") (pintype "input"))
      (node (ref "E43") (pin "8") (pinfunction "~{Q}_8") (pintype "output"))
      (node (ref "E47") (pin "13") (pinfunction "I2_13") (pintype "input"))
      (node (ref "E48") (pin "12") (pinfunction "I2_12") (pintype "input"))
    )
    (net (code "179") (name "Net-(E43A-D)") (class "Default")
      (node (ref "E43") (pin "2") (pinfunction "D_2") (pintype "input"))
      (node (ref "E43") (pin "6") (pinfunction "~{Q}_6") (pintype "output"))
      (node (ref "E47") (pin "1") (pinfunction "I0_1") (pintype "input"))
      (node (ref "E48") (pin "9") (pinfunction "I0_9") (pintype "input"))
    )
    (net (code "180") (name "Net-(E44A-CKB)") (class "Default")
      (node (ref "E44") (pin "1") (pinfunction "CKB_1") (pintype "input"))
      (node (ref "E44") (pin "12") (pinfunction "QA_12") (pintype "output"))
    )
    (net (code "181") (name "Net-(E44A-R0(1))") (class "Default")
      (node (ref "E44") (pin "2") (pinfunction "R0(1)_2") (pintype "input"))
      (node (ref "E44") (pin "3") (pinfunction "R0(2)_3") (pintype "input"))
      (node (ref "E54") (pin "3") (pinfunction "O_3") (pintype "output"))
    )
    (net (code "182") (name "Net-(E45A-RC)") (class "Default")
      (node (ref "C57") (pin "1") (pinfunction "1_1") (pintype "passive"))
      (node (ref "E45") (pin "2") (pinfunction "RC_2") (pintype "input"))
    )
    (net (code "183") (name "Net-(E47A-I1)") (class "Default")
      (node (ref "E47") (pin "2") (pinfunction "I1_2") (pintype "input"))
      (node (ref "E49") (pin "2") (pinfunction "O_2") (pintype "output"))
    )
    (net (code "184") (name "Net-(E47A-O)") (class "Default")
      (node (ref "E47") (pin "12") (pinfunction "O_12") (pintype "output"))
      (node (ref "E54") (pin "10") (pinfunction "I1_10") (pintype "input"))
    )
    (net (code "185") (name "Net-(E48B-I1)") (class "Default")
      (node (ref "E48") (pin "10") (pinfunction "I1_10") (pintype "input"))
      (node (ref "E49") (pin "4") (pinfunction "O_4") (pintype "output"))
    )
    (net (code "186") (name "Net-(E48B-O)") (class "Default")
      (node (ref "E48") (pin "8") (pinfunction "O_8") (pintype "output"))
      (node (ref "E54") (pin "9") (pinfunction "I0_9") (pintype "input"))
    )
    (net (code "187") (name "Net-(E49C-O)") (class "Default")
      (node (ref "E49") (pin "6") (pinfunction "O_6") (pintype "output"))
      (node (ref "E57") (pin "4") (pinfunction "PRE_4") (pintype "input"))
    )
    (net (code "188") (name "Net-(E49E-I)") (class "Default")
      (node (ref "C67") (pin "1") (pinfunction "1_1") (pintype "passive"))
      (node (ref "E49") (pin "11") (pinfunction "I_11") (pintype "input"))
      (node (ref "E55") (pin "13") (pinfunction "O_13") (pintype "output"))
      (node (ref "R57") (pin "1") (pinfunction "1_1") (pintype "passive"))
      (node (ref "R58") (pin "1") (pinfunction "1_1") (pintype "passive"))
    )
    (net (code "189") (name "Net-(E49E-O)") (class "Default")
      (node (ref "E49") (pin "10") (pinfunction "O_10") (pintype "output"))
      (node (ref "E50") (pin "2") (pinfunction "I_2") (pintype "input"))
    )
    (net (code "190") (name "Net-(E51A-I1)") (class "Default")
      (node (ref "E51") (pin "11") (pinfunction "I0_11") (pintype "input"))
      (node (ref "E51") (pin "14") (pinfunction "O_14") (pintype "output"))
      (node (ref "E51") (pin "5") (pinfunction "I1_5") (pintype "input"))
    )
    (net (code "191") (name "Net-(E51B-I1)") (class "Default")
      (node (ref "E51") (pin "13") (pinfunction "O_13") (pintype "output"))
      (node (ref "E51") (pin "7") (pinfunction "I1_7") (pintype "input"))
      (node (ref "E51") (pin "9") (pinfunction "I0_9") (pintype "input"))
    )
    (net (code "192") (name "Net-(E51C-I1)") (class "Default")
      (node (ref "E51") (pin "10") (pinfunction "I1_10") (pintype "input"))
      (node (ref "R19") (pin "2") (pinfunction "2_2") (pintype "passive"))
      (node (ref "R56") (pin "1") (pinfunction "1_1") (pintype "passive"))
    )
    (net (code "193") (name "Net-(E51D-I1)") (class "Default")
      (node (ref "E51") (pin "12") (pinfunction "I1_12") (pintype "input"))
      (node (ref "Q3") (pin "3") (pinfunction "C_3") (pintype "passive"))
      (node (ref "R20") (pin "2") (pinfunction "2_2") (pintype "passive"))
    )
    (net (code "194") (name "Net-(E54C-O)") (class "Default")
      (node (ref "E54") (pin "8") (pinfunction "O_8") (pintype "output"))
      (node (ref "E57") (pin "11") (pinfunction "CLK_11") (pintype "input"))
    )
    (net (code "195") (name "Net-(E54D-I1)") (class "Default")
      (node (ref "E54") (pin "13") (pinfunction "I1_13") (pintype "input"))
      (node (ref "E7") (pin "9") (pinfunction "I0_9") (pintype "input"))
      (node (ref "E8") (pin "9") (pinfunction "QB_9") (pintype "output"))
    )
    (net (code "196") (name "Net-(E55A-O)") (class "Default")
      (node (ref "E55") (pin "3") (pinfunction "O_3") (pintype "output"))
      (node (ref "E56") (pin "12") (pinfunction "D_12") (pintype "input"))
    )
    (net (code "197") (name "Net-(E55B-O)") (class "Default")
      (node (ref "E55") (pin "2") (pinfunction "O_2") (pintype "output"))
      (node (ref "E56") (pin "2") (pinfunction "D_2") (pintype "input"))
    )
    (net (code "198") (name "Net-(Q1-B)") (class "Default")
      (node (ref "Q1") (pin "2") (pinfunction "B_2") (pintype "passive"))
      (node (ref "R41") (pin "2") (pinfunction "2_2") (pintype "passive"))
    )
    (net (code "199") (name "Net-(Q1-C)") (class "Default")
      (node (ref "Q1") (pin "3") (pinfunction "C_3") (pintype "passive"))
      (node (ref "R19") (pin "1") (pinfunction "1_1") (pintype "passive"))
    )
    (net (code "200") (name "Net-(Q2-B)") (class "Default")
      (node (ref "Q2") (pin "2") (pinfunction "B_2") (pintype "passive"))
      (node (ref "R39") (pin "2") (pinfunction "2_2") (pintype "passive"))
      (node (ref "R54") (pin "1") (pinfunction "1_1") (pintype "passive"))
    )
    (net (code "201") (name "Net-(Q2-C)") (class "Default")
      (node (ref "Q2") (pin "3") (pinfunction "C_3") (pintype "passive"))
      (node (ref "R52") (pin "1") (pinfunction "1_1") (pintype "passive"))
    )
    (net (code "202") (name "Net-(Q2-E)") (class "Default")
      (node (ref "Q2") (pin "1") (pinfunction "E_1") (pintype "passive"))
      (node (ref "R41") (pin "1") (pinfunction "1_1") (pintype "passive"))
      (node (ref "R59") (pin "2") (pinfunction "2_2") (pintype "passive"))
    )
    (net (code "203") (name "Net-(Q3-B)") (class "Default")
      (node (ref "Q3") (pin "2") (pinfunction "B_2") (pintype "passive"))
      (node (ref "R38") (pin "2") (pinfunction "2_2") (pintype "passive"))
    )
    (net (code "204") (name "Net-(Q4-B)") (class "Default")
      (node (ref "Q4") (pin "2") (pinfunction "B_2") (pintype "passive"))
      (node (ref "R40") (pin "1") (pinfunction "1_1") (pintype "passive"))
      (node (ref "R54") (pin "2") (pinfunction "2_2") (pintype "passive"))
    )
    (net (code "205") (name "Net-(Q4-C)") (class "Default")
      (node (ref "Q4") (pin "3") (pinfunction "C_3") (pintype "passive"))
      (node (ref "R38") (pin "1") (pinfunction "1_1") (pintype "passive"))
      (node (ref "R53") (pin "1") (pinfunction "1_1") (pintype "passive"))
    )
    (net (code "206") (name "Net-(Q4-E)") (class "Default")
      (node (ref "Q4") (pin "1") (pinfunction "E_1") (pintype "passive"))
      (node (ref "R51") (pin "1") (pinfunction "1_1") (pintype "passive"))
    )
    (net (code "207") (name "Net-(Q5-B)") (class "Default")
      (node (ref "C67") (pin "2") (pinfunction "2_2") (pintype "passive"))
      (node (ref "Q5") (pin "2") (pinfunction "B_2") (pintype "passive"))
      (node (ref "R58") (pin "2") (pinfunction "2_2") (pintype "passive"))
    )
    (net (code "208") (name "Net-(Q5-C)") (class "Default")
      (node (ref "Q5") (pin "3") (pinfunction "C_3") (pintype "passive"))
      (node (ref "R55") (pin "1") (pinfunction "1_1") (pintype "passive"))
    )
    (net (code "209") (name "Net-(Q5-E)") (class "Default")
      (node (ref "Q5") (pin "1") (pinfunction "E_1") (pintype "passive"))
      (node (ref "Q6") (pin "2") (pinfunction "B_2") (pintype "passive"))
      (node (ref "R42") (pin "1") (pinfunction "1_1") (pintype "passive"))
    )
    (net (code "210") (name "Net-(Q6-E)") (class "Default")
      (node (ref "Q6") (pin "1") (pinfunction "E_1") (pintype "passive"))
      (node (ref "R46") (pin "1") (pinfunction "1_1") (pintype "passive"))
    )
    (net (code "211") (name "Net-(Q7-B)") (class "Default")
      (node (ref "Q7") (pin "2") (pinfunction "B_2") (pintype "passive"))
      (node (ref "R43") (pin "2") (pinfunction "2_2") (pintype "passive"))
      (node (ref "R55") (pin "2") (pinfunction "2_2") (pintype "passive"))
    )
    (net (code "212") (name "Net-(Q7-E)") (class "Default")
      (node (ref "Q7") (pin "1") (pinfunction "E_1") (pintype "passive"))
      (node (ref "R47") (pin "2") (pinfunction "2_2") (pintype "passive"))
    )
    (net (code "213") (name "Net-(Q8-B)") (class "Default")
      (node (ref "D2") (pin "C") (pinfunction "C_C") (pintype "passive"))
      (node (ref "Q8") (pin "2") (pinfunction "B_2") (pintype "passive"))
      (node (ref "R18") (pin "2") (pinfunction "2_2") (pintype "passive"))
    )
    (net (code "214") (name "Net-(Q8-E)") (class "Default")
      (node (ref "Q8") (pin "1") (pinfunction "E_1") (pintype "passive"))
      (node (ref "R48") (pin "1") (pinfunction "1_1") (pintype "passive"))
    )
    (net (code "215") (name "Net-(R13-Pad1)") (class "Default")
      (node (ref "R13") (pin "1") (pinfunction "1_1") (pintype "passive"))
      (node (ref "R13") (pin "2") (pinfunction "2_2") (pintype "passive"))
      (node (ref "X0") (pin "2") (pinfunction "2_2") (pintype "passive"))
    )
    (net (code "216") (name "Net-(R34-Pad2)") (class "Default")
      (node (ref "R34") (pin "2") (pinfunction "2_2") (pintype "passive"))
      (node (ref "X0") (pin "1") (pinfunction "1_1") (pintype "passive"))
    )
    (net (code "217") (name "Net-(R49-Pad1)") (class "Default")
      (node (ref "R49") (pin "1") (pinfunction "1_1") (pintype "passive"))
      (node (ref "R51") (pin "2") (pinfunction "2_2") (pintype "passive"))
      (node (ref "TTY") (pin "1") (pinfunction "1_1") (pintype "passive"))
      (node (ref "W1") (pin "1") (pinfunction "1_1") (pintype "passive"))
    )
    (net (code "218") (name "Net-(Y1A-TS)") (class "Default")
      (node (ref "Y1A") (pin "1") (pinfunction "TS_1") (pintype "passive"))
      (node (ref "Y1B") (pin "1") (pinfunction "TS_1") (pintype "passive"))
    )
    (net (code "219") (name "OVERRUN_ERR") (class "Default")
      (node (ref "E11") (pin "2") (pinfunction "I0_2") (pintype "input"))
      (node (ref "E13") (pin "1") (pinfunction "I0_1") (pintype "input"))
      (node (ref "E19") (pin "15") (pinfunction "OR_15") (pintype "tri_state"))
    )
    (net (code "220") (name "P1.18US") (class "Default")
      (node (ref "E16") (pin "3") (pinfunction "I_3") (pintype "input"))
      (node (ref "E21") (pin "4") (pinfunction "I0_4") (pintype "input"))
      (node (ref "E7") (pin "13") (pinfunction "I1_13") (pintype "input"))
      (node (ref "E8") (pin "11") (pinfunction "QD_11") (pintype "output"))
    )
    (net (code "221") (name "PARITY_ERR") (class "Default")
      (node (ref "E11") (pin "11") (pinfunction "I0_11") (pintype "input"))
      (node (ref "E13") (pin "4") (pinfunction "I2_4") (pintype "input"))
      (node (ref "E19") (pin "13") (pinfunction "PE_13") (pintype "tri_state"))
    )
    (net (code "222") (name "POWER_OK") (class "Default")
      (node (ref "E55") (pin "9") (pinfunction "I0_9") (pintype "input"))
      (node (ref "U$2") (pin "BV2") (pinfunction "1_BV2") (pintype "bidirectional"))
    )
    (net (code "223") (name "R=150") (class "Default")
      (node (ref "E16") (pin "13") (pinfunction "I_13") (pintype "input"))
      (node (ref "E21") (pin "12") (pinfunction "I0_12") (pintype "input"))
      (node (ref "E28") (pin "7") (pinfunction "7_7") (pintype "passive"))
      (node (ref "R25") (pin "1") (pinfunction "1_1") (pintype "passive"))
      (node (ref "SP1") (pin "15") (pinfunction "2_15") (pintype "passive"))
    )
    (net (code "224") (name "RD0") (class "Default")
      (node (ref "E19") (pin "12") (pinfunction "RD1_12") (pintype "tri_state"))
      (node (ref "E29") (pin "2") (pinfunction "I0_2") (pintype "input"))
    )
    (net (code "225") (name "RD1") (class "Default")
      (node (ref "E19") (pin "11") (pinfunction "RD2_11") (pintype "tri_state"))
      (node (ref "E29") (pin "5") (pinfunction "I0_5") (pintype "input"))
    )
    (net (code "226") (name "RD2") (class "Default")
      (node (ref "E19") (pin "10") (pinfunction "RD3_10") (pintype "tri_state"))
      (node (ref "E29") (pin "12") (pinfunction "I1_12") (pintype "input"))
    )
    (net (code "227") (name "RD3") (class "Default")
      (node (ref "E19") (pin "9") (pinfunction "RD4_9") (pintype "tri_state"))
      (node (ref "E29") (pin "9") (pinfunction "I1_9") (pintype "input"))
    )
    (net (code "228") (name "RD4") (class "Default")
      (node (ref "E19") (pin "8") (pinfunction "RD5_8") (pintype "tri_state"))
      (node (ref "E23") (pin "2") (pinfunction "I0_2") (pintype "input"))
    )
    (net (code "229") (name "RD5") (class "Default")
      (node (ref "E19") (pin "7") (pinfunction "RD6_7") (pintype "tri_state"))
      (node (ref "E23") (pin "5") (pinfunction "I0_5") (pintype "input"))
    )
    (net (code "230") (name "RD6") (class "Default")
      (node (ref "E19") (pin "6") (pinfunction "RD7_6") (pintype "tri_state"))
      (node (ref "E23") (pin "12") (pinfunction "I1_12") (pintype "input"))
    )
    (net (code "231") (name "RD7") (class "Default")
      (node (ref "E19") (pin "5") (pinfunction "RD8_5") (pintype "tri_state"))
      (node (ref "E23") (pin "9") (pinfunction "I1_9") (pintype "input"))
    )
    (net (code "232") (name "READER_RUN+") (class "Default")
      (node (ref "D4") (pin "C") (pinfunction "C_C") (pintype "passive"))
      (node (ref "J1") (pin "PP") (pinfunction "35_PP") (pintype "bidirectional"))
      (node (ref "Q8") (pin "3") (pinfunction "C_3") (pintype "passive"))
    )
    (net (code "233") (name "READER_RUN-") (class "Default")
      (node (ref "J1") (pin "EE") (pinfunction "27_EE") (pintype "bidirectional"))
      (node (ref "R45") (pin "2") (pinfunction "2_2") (pintype "passive"))
    )
    (net (code "234") (name "RECV_0") (class "Default")
      (node (ref "E40") (pin "1") (pinfunction "I0_1") (pintype "input"))
      (node (ref "E41") (pin "1") (pinfunction "O0_1") (pintype "output"))
    )
    (net (code "235") (name "RECV_1") (class "Default")
      (node (ref "E32") (pin "1") (pinfunction "I_1") (pintype "input"))
      (node (ref "E41") (pin "2") (pinfunction "O1_2") (pintype "output"))
    )
    (net (code "236") (name "RECV_5") (class "Default")
      (node (ref "E35") (pin "11") (pinfunction "I0_11") (pintype "input"))
      (node (ref "E41") (pin "4") (pinfunction "O3_4") (pintype "output"))
      (node (ref "E55") (pin "5") (pinfunction "I1_5") (pintype "input"))
      (node (ref "E55") (pin "6") (pinfunction "I0_6") (pintype "input"))
      (node (ref "R26") (pin "2") (pinfunction "2_2") (pintype "passive"))
    )
    (net (code "237") (name "RECV_246") (class "Default")
      (node (ref "E13") (pin "13") (pinfunction "I3_13") (pintype "input"))
      (node (ref "E35") (pin "3") (pinfunction "I1_3") (pintype "input"))
      (node (ref "E41") (pin "3") (pinfunction "O2_3") (pintype "output"))
    )
    (net (code "238") (name "RFLAG_H") (class "Default")
      (node (ref "E27") (pin "6") (pinfunction "~{Q}_6") (pintype "output"))
      (node (ref "E33") (pin "2") (pinfunction "I0_2") (pintype "input"))
    )
    (net (code "239") (name "RFLAG_L") (class "Default")
      (node (ref "E27") (pin "5") (pinfunction "Q_5") (pintype "output"))
      (node (ref "E38") (pin "12") (pinfunction "I0_12") (pintype "input"))
    )
    (net (code "240") (name "RTSDTR") (class "Default")
      (node (ref "E50") (pin "6") (pinfunction "O_6") (pintype "output"))
      (node (ref "J1") (pin "DD") (pinfunction "26_DD") (pintype "bidirectional"))
      (node (ref "J1") (pin "Y") (pinfunction "21_Y") (pintype "bidirectional"))
    )
    (net (code "241") (name "RX20MA_DATA") (class "Default")
      (node (ref "E51") (pin "2") (pinfunction "O_2") (pintype "output"))
      (node (ref "E51") (pin "4") (pinfunction "I0_4") (pintype "input"))
      (node (ref "J1") (pin "H") (pinfunction "7_H") (pintype "bidirectional"))
    )
    (net (code "242") (name "RX_20MA+") (class "Default")
      (node (ref "J1") (pin "K") (pinfunction "9_K") (pintype "bidirectional"))
      (node (ref "R49") (pin "2") (pinfunction "2_2") (pintype "passive"))
    )
    (net (code "243") (name "RX_20MA-") (class "Default")
      (node (ref "J1") (pin "S") (pinfunction "15_S") (pintype "bidirectional"))
      (node (ref "R50") (pin "2") (pinfunction "2_2") (pintype "passive"))
    )
    (net (code "244") (name "RX_CLK") (class "Default")
      (node (ref "E19") (pin "17") (pinfunction "RCP_17") (pintype "input"))
      (node (ref "E21") (pin "3") (pinfunction "O_3") (pintype "output"))
      (node (ref "E44") (pin "14") (pinfunction "CKA_14") (pintype "input"))
    )
    (net (code "245") (name "RX_DATA") (class "Default")
      (node (ref "E45") (pin "3") (pinfunction "O_3") (pintype "output"))
      (node (ref "J1") (pin "M") (pinfunction "11_M") (pintype "bidirectional"))
    )
    (net (code "246") (name "RX_DATA_AV") (class "Default")
      (node (ref "E19") (pin "19") (pinfunction "DAV_19") (pintype "tri_state"))
      (node (ref "E46") (pin "10") (pinfunction "I1_10") (pintype "input"))
      (node (ref "E46") (pin "9") (pinfunction "I0_9") (pintype "input"))
    )
    (net (code "247") (name "SELECTED_H") (class "Default")
      (node (ref "E12") (pin "2") (pinfunction "O_2") (pintype "output"))
      (node (ref "E34") (pin "5") (pinfunction "I0_5") (pintype "input"))
      (node (ref "E47") (pin "11") (pinfunction "I2_11") (pintype "input"))
      (node (ref "E54") (pin "4") (pinfunction "I0_4") (pintype "input"))
      (node (ref "E54") (pin "5") (pinfunction "I1_5") (pintype "input"))
    )
    (net (code "248") (name "SELECTED_L") (class "Default")
      (node (ref "E52") (pin "10") (pinfunction "I1_10") (pintype "input"))
      (node (ref "E52") (pin "5") (pinfunction "I1_5") (pintype "input"))
      (node (ref "E52") (pin "6") (pinfunction "I0_6") (pintype "input"))
      (node (ref "E54") (pin "6") (pinfunction "O_6") (pintype "output"))
    )
    (net (code "249") (name "SERIAL_IN") (class "Default")
      (node (ref "E19") (pin "20") (pinfunction "SI_20") (pintype "input"))
      (node (ref "J1") (pin "E") (pinfunction "5_E") (pintype "bidirectional"))
    )
    (net (code "250") (name "SERIAL_OUT") (class "Default")
      (node (ref "E19") (pin "25") (pinfunction "SO_25") (pintype "output"))
      (node (ref "E55") (pin "11") (pinfunction "I0_11") (pintype "input"))
    )
    (net (code "251") (name "SKIP_L") (class "Default")
      (node (ref "E33") (pin "1") (pinfunction "O_1") (pintype "open_collector"))
      (node (ref "E33") (pin "10") (pinfunction "O_10") (pintype "open_collector"))
      (node (ref "E33") (pin "13") (pinfunction "O_13") (pintype "open_collector"))
      (node (ref "U$2") (pin "CS1") (pinfunction "1_CS1") (pintype "bidirectional"))
    )
    (net (code "252") (name "STAT_ENAB_L") (class "Default")
      (node (ref "E53") (pin "10") (pinfunction "I1_10") (pintype "input"))
      (node (ref "E56") (pin "8") (pinfunction "~{Q}_8") (pintype "output"))
    )
    (net (code "253") (name "SWD") (class "Default")
      (node (ref "E28") (pin "1") (pinfunction "1_1") (pintype "passive"))
      (node (ref "E53") (pin "9") (pinfunction "I0_9") (pintype "input"))
      (node (ref "R21") (pin "1") (pinfunction "1_1") (pintype "passive"))
      (node (ref "SWD") (pin "2") (pinfunction "2_2") (pintype "passive"))
      (node (ref "W3") (pin "2") (pinfunction "2_2") (pintype "passive"))
    )
    (net (code "254") (name "TCLKI") (class "Default")
      (node (ref "E28") (pin "4") (pinfunction "4_4") (pintype "passive"))
      (node (ref "E3") (pin "1") (pinfunction "I0_1") (pintype "input"))
      (node (ref "R23") (pin "1") (pinfunction "1_1") (pintype "passive"))
    )
    (net (code "255") (name "TCLKO") (class "Default")
      (node (ref "E28") (pin "8") (pinfunction "8_8") (pintype "passive"))
      (node (ref "E3") (pin "11") (pinfunction "O_11") (pintype "output"))
      (node (ref "E3") (pin "2") (pinfunction "I1_2") (pintype "input"))
    )
    (net (code "256") (name "TEST_SYNC") (class "Default")
      (node (ref "E27") (pin "12") (pinfunction "D_12") (pintype "input"))
      (node (ref "E27") (pin "13") (pinfunction "CLR_13") (pintype "input"))
      (node (ref "E28") (pin "9") (pinfunction "9_9") (pintype "passive"))
      (node (ref "R24") (pin "1") (pinfunction "1_1") (pintype "passive"))
    )
    (net (code "257") (name "TFLAG_H") (class "Default")
      (node (ref "E33") (pin "12") (pinfunction "I1_12") (pintype "input"))
      (node (ref "E57") (pin "5") (pinfunction "Q_5") (pintype "output"))
    )
    (net (code "258") (name "TFLAG_L") (class "Default")
      (node (ref "E38") (pin "13") (pinfunction "I1_13") (pintype "input"))
      (node (ref "E57") (pin "6") (pinfunction "~{Q}_6") (pintype "output"))
    )
    (net (code "259") (name "TP3") (class "Default")
      (node (ref "E52") (pin "12") (pinfunction "I1_12") (pintype "input"))
      (node (ref "U$2") (pin "CH2") (pinfunction "1_CH2") (pintype "bidirectional"))
    )
    (net (code "260") (name "TRANS_0") (class "Default")
      (node (ref "E37") (pin "9") (pinfunction "I1_9") (pintype "input"))
      (node (ref "E41") (pin "5") (pinfunction "O4_5") (pintype "output"))
    )
    (net (code "261") (name "TRANS_1") (class "Default")
      (node (ref "E32") (pin "11") (pinfunction "I_11") (pintype "input"))
      (node (ref "E41") (pin "6") (pinfunction "O5_6") (pintype "output"))
    )
    (net (code "262") (name "TRANS_5") (class "Default")
      (node (ref "E41") (pin "9") (pinfunction "O7_9") (pintype "output"))
      (node (ref "E53") (pin "4") (pinfunction "I2_4") (pintype "input"))
      (node (ref "E53") (pin "5") (pinfunction "I3_5") (pintype "input"))
    )
    (net (code "263") (name "TRANS_246") (class "Default")
      (node (ref "E35") (pin "6") (pinfunction "I1_6") (pintype "input"))
      (node (ref "E35") (pin "8") (pinfunction "I0_8") (pintype "input"))
      (node (ref "E41") (pin "7") (pinfunction "O6_7") (pintype "output"))
    )
    (net (code "264") (name "TSB") (class "Default")
      (node (ref "E19") (pin "36") (pinfunction "TSB_36") (pintype "input"))
      (node (ref "E6") (pin "1") (pinfunction "1_1") (pintype "passive"))
      (node (ref "R29") (pin "1") (pinfunction "1_1") (pintype "passive"))
      (node (ref "SB") (pin "2") (pinfunction "2_2") (pintype "passive"))
      (node (ref "W4") (pin "2") (pinfunction "2_2") (pintype "passive"))
    )
    (net (code "265") (name "TXD_STROBE") (class "Default")
      (node (ref "E19") (pin "23") (pinfunction "/DS_23") (pintype "input"))
      (node (ref "E49") (pin "3") (pinfunction "I_3") (pintype "input"))
      (node (ref "E54") (pin "11") (pinfunction "O_11") (pintype "output"))
    )
    (net (code "266") (name "TX_20MA+") (class "Default")
      (node (ref "J1") (pin "AA") (pinfunction "23_AA") (pintype "bidirectional"))
      (node (ref "Q6") (pin "3") (pinfunction "C_3") (pintype "passive"))
    )
    (net (code "267") (name "TX_20MA-") (class "Default")
      (node (ref "J1") (pin "KK") (pinfunction "31_KK") (pintype "bidirectional"))
      (node (ref "Q7") (pin "3") (pinfunction "C_3") (pintype "passive"))
    )
    (net (code "268") (name "TX_BUF_EMPTY") (class "Default")
      (node (ref "E19") (pin "22") (pinfunction "TBMT_22") (pintype "tri_state"))
      (node (ref "E46") (pin "4") (pinfunction "I0_4") (pintype "input"))
      (node (ref "E46") (pin "5") (pinfunction "I1_5") (pintype "input"))
    )
    (net (code "269") (name "TX_CLK") (class "Default")
      (node (ref "E19") (pin "40") (pinfunction "TCP_40") (pintype "input"))
      (node (ref "E21") (pin "13") (pinfunction "I1_13") (pintype "input"))
      (node (ref "E22") (pin "5") (pinfunction "Y_5") (pintype "output"))
    )
    (net (code "270") (name "VCC") (class "Default")
      (node (ref "C1") (pin "1") (pinfunction "1_1") (pintype "passive"))
      (node (ref "C10") (pin "1") (pinfunction "1_1") (pintype "passive"))
      (node (ref "C11") (pin "1") (pinfunction "1_1") (pintype "passive"))
      (node (ref "C12") (pin "1") (pinfunction "1_1") (pintype "passive"))
      (node (ref "C13") (pin "1") (pinfunction "1_1") (pintype "passive"))
      (node (ref "C14") (pin "1") (pinfunction "1_1") (pintype "passive"))
      (node (ref "C15") (pin "1") (pinfunction "1_1") (pintype "passive"))
      (node (ref "C16") (pin "1") (pinfunction "1_1") (pintype "passive"))
      (node (ref "C17") (pin "1") (pinfunction "1_1") (pintype "passive"))
      (node (ref "C19") (pin "1") (pinfunction "1_1") (pintype "passive"))
      (node (ref "C2") (pin "1") (pinfunction "1_1") (pintype "passive"))
      (node (ref "C20") (pin "1") (pinfunction "1_1") (pintype "passive"))
      (node (ref "C21") (pin "1") (pinfunction "1_1") (pintype "passive"))
      (node (ref "C22") (pin "1") (pinfunction "1_1") (pintype "passive"))
      (node (ref "C23") (pin "1") (pinfunction "1_1") (pintype "passive"))
      (node (ref "C24") (pin "1") (pinfunction "1_1") (pintype "passive"))
      (node (ref "C25") (pin "1") (pinfunction "1_1") (pintype "passive"))
      (node (ref "C26") (pin "1") (pinfunction "1_1") (pintype "passive"))
      (node (ref "C27") (pin "1") (pinfunction "1_1") (pintype "passive"))
      (node (ref "C28") (pin "1") (pinfunction "1_1") (pintype "passive"))
      (node (ref "C29") (pin "1") (pinfunction "1_1") (pintype "passive"))
      (node (ref "C3") (pin "1") (pinfunction "1_1") (pintype "passive"))
      (node (ref "C30") (pin "1") (pinfunction "1_1") (pintype "passive"))
      (node (ref "C31") (pin "1") (pinfunction "1_1") (pintype "passive"))
      (node (ref "C32") (pin "1") (pinfunction "1_1") (pintype "passive"))
      (node (ref "C33") (pin "1") (pinfunction "1_1") (pintype "passive"))
      (node (ref "C34") (pin "1") (pinfunction "1_1") (pintype "passive"))
      (node (ref "C35") (pin "1") (pinfunction "1_1") (pintype "passive"))
      (node (ref "C36") (pin "1") (pinfunction "1_1") (pintype "passive"))
      (node (ref "C37") (pin "1") (pinfunction "1_1") (pintype "passive"))
      (node (ref "C38") (pin "1") (pinfunction "1_1") (pintype "passive"))
      (node (ref "C39") (pin "1") (pinfunction "1_1") (pintype "passive"))
      (node (ref "C4") (pin "1") (pinfunction "1_1") (pintype "passive"))
      (node (ref "C40") (pin "1") (pinfunction "1_1") (pintype "passive"))
      (node (ref "C41") (pin "1") (pinfunction "1_1") (pintype "passive"))
      (node (ref "C42") (pin "1") (pinfunction "1_1") (pintype "passive"))
      (node (ref "C43") (pin "1") (pinfunction "1_1") (pintype "passive"))
      (node (ref "C44") (pin "1") (pinfunction "1_1") (pintype "passive"))
      (node (ref "C45") (pin "1") (pinfunction "1_1") (pintype "passive"))
      (node (ref "C46") (pin "1") (pinfunction "1_1") (pintype "passive"))
      (node (ref "C47") (pin "1") (pinfunction "1_1") (pintype "passive"))
      (node (ref "C48") (pin "1") (pinfunction "1_1") (pintype "passive"))
      (node (ref "C49") (pin "1") (pinfunction "1_1") (pintype "passive"))
      (node (ref "C5") (pin "1") (pinfunction "1_1") (pintype "passive"))
      (node (ref "C50") (pin "1") (pinfunction "1_1") (pintype "passive"))
      (node (ref "C51") (pin "1") (pinfunction "1_1") (pintype "passive"))
      (node (ref "C52") (pin "1") (pinfunction "1_1") (pintype "passive"))
      (node (ref "C59") (pin "+") (pinfunction "+_+") (pintype "passive"))
      (node (ref "C6") (pin "1") (pinfunction "1_1") (pintype "passive"))
      (node (ref "C60") (pin "+") (pinfunction "+_+") (pintype "passive"))
      (node (ref "C61") (pin "+") (pinfunction "+_+") (pintype "passive"))
      (node (ref "C7") (pin "1") (pinfunction "1_1") (pintype "passive"))
      (node (ref "C8") (pin "1") (pinfunction "1_1") (pintype "passive"))
      (node (ref "C9") (pin "1") (pinfunction "1_1") (pintype "passive"))
      (node (ref "D3") (pin "A") (pinfunction "A_A") (pintype "passive"))
      (node (ref "D7") (pin "A") (pinfunction "A_A") (pintype "passive"))
      (node (ref "E19") (pin "1") (pinfunction "VCC_1") (pintype "power_in"))
      (node (ref "Q3") (pin "1") (pinfunction "E_1") (pintype "passive"))
      (node (ref "R26") (pin "1") (pinfunction "1_1") (pintype "passive"))
      (node (ref "R27") (pin "1") (pinfunction "1_1") (pintype "passive"))
      (node (ref "R33") (pin "2") (pinfunction "2_2") (pintype "passive"))
      (node (ref "R40") (pin "2") (pinfunction "2_2") (pintype "passive"))
      (node (ref "R42") (pin "2") (pinfunction "2_2") (pintype "passive"))
      (node (ref "R46") (pin "2") (pinfunction "2_2") (pintype "passive"))
      (node (ref "R48") (pin "2") (pinfunction "2_2") (pintype "passive"))
      (node (ref "R53") (pin "2") (pinfunction "2_2") (pintype "passive"))
      (node (ref "R56") (pin "2") (pinfunction "2_2") (pintype "passive"))
      (node (ref "R57") (pin "2") (pinfunction "2_2") (pintype "passive"))
      (node (ref "R60") (pin "2") (pinfunction "2_2") (pintype "passive"))
      (node (ref "R61") (pin "2") (pinfunction "2_2") (pintype "passive"))
      (node (ref "U$2") (pin "AA2") (pinfunction "1_AA2") (pintype "bidirectional"))
      (node (ref "U$2") (pin "BA2") (pinfunction "1_BA2") (pintype "bidirectional"))
      (node (ref "U$2") (pin "CA2") (pinfunction "1_CA2") (pintype "bidirectional"))
      (node (ref "Y1A") (pin "14") (pinfunction "VCC_14") (pintype "power_in"))
      (node (ref "Y1B") (pin "8") (pinfunction "VCC_8") (pintype "power_in"))
    )
    (net (code "271") (name "unconnected-(E6-Pad3)") (class "Default")
      (node (ref "E6") (pin "3") (pinfunction "3_3") (pintype "passive"))
    )
    (net (code "272") (name "unconnected-(E6-Pad4)") (class "Default")
      (node (ref "E6") (pin "4") (pinfunction "4_4") (pintype "passive"))
    )
    (net (code "273") (name "unconnected-(E6-Pad5)") (class "Default")
      (node (ref "E6") (pin "5") (pinfunction "5_5") (pintype "passive"))
    )
    (net (code "274") (name "unconnected-(E6-Pad6)") (class "Default")
      (node (ref "E6") (pin "6") (pinfunction "6_6") (pintype "passive"))
    )
    (net (code "275") (name "unconnected-(E6-Pad7)") (class "Default")
      (node (ref "E6") (pin "7") (pinfunction "7_7") (pintype "passive"))
    )
    (net (code "276") (name "unconnected-(E6-Pad8)") (class "Default")
      (node (ref "E6") (pin "8") (pinfunction "8_8") (pintype "passive"))
    )
    (net (code "277") (name "unconnected-(E6-Pad9)") (class "Default")
      (node (ref "E6") (pin "9") (pinfunction "9_9") (pintype "passive"))
    )
    (net (code "278") (name "unconnected-(E6-Pad10)") (class "Default")
      (node (ref "E6") (pin "10") (pinfunction "10_10") (pintype "passive"))
    )
    (net (code "279") (name "unconnected-(E6-Pad11)") (class "Default")
      (node (ref "E6") (pin "11") (pinfunction "11_11") (pintype "passive"))
    )
    (net (code "280") (name "unconnected-(E6-Pad12)") (class "Default")
      (node (ref "E6") (pin "12") (pinfunction "12_12") (pintype "passive"))
    )
    (net (code "281") (name "unconnected-(E6-Pad13)") (class "Default")
      (node (ref "E6") (pin "13") (pinfunction "13_13") (pintype "passive"))
    )
    (net (code "282") (name "unconnected-(E6-Pad14)") (class "Default")
      (node (ref "E6") (pin "14") (pinfunction "14_14") (pintype "passive"))
    )
    (net (code "283") (name "unconnected-(E9A-QB-Pad11)") (class "Default")
      (node (ref "E9") (pin "11") (pinfunction "QB_11") (pintype "output"))
    )
    (net (code "284") (name "unconnected-(E9A-QC-Pad9)") (class "Default")
      (node (ref "E9") (pin "9") (pinfunction "QC_9") (pintype "output"))
    )
    (net (code "285") (name "unconnected-(E14A-QB-Pad9)") (class "Default")
      (node (ref "E14") (pin "9") (pinfunction "QB_9") (pintype "output"))
    )
    (net (code "286") (name "unconnected-(E14A-QC-Pad8)") (class "Default")
      (node (ref "E14") (pin "8") (pinfunction "QC_8") (pintype "output"))
    )
    (net (code "287") (name "unconnected-(E17A-QB-Pad9)") (class "Default")
      (node (ref "E17") (pin "9") (pinfunction "QB_9") (pintype "output"))
    )
    (net (code "288") (name "unconnected-(E17A-QC-Pad8)") (class "Default")
      (node (ref "E17") (pin "8") (pinfunction "QC_8") (pintype "output"))
    )
    (net (code "289") (name "unconnected-(E19A-EOC-Pad24)") (class "Default")
      (node (ref "E19") (pin "24") (pinfunction "EOC_24") (pintype "output"))
    )
    (net (code "290") (name "unconnected-(E20A-~{Q}-Pad6)") (class "Default")
      (node (ref "E20") (pin "6") (pinfunction "~{Q}_6") (pintype "output"))
    )
    (net (code "291") (name "unconnected-(E25A-~{Q3}-Pad11)") (class "Default")
      (node (ref "E25") (pin "11") (pinfunction "~{Q3}_11") (pintype "output"))
    )
    (net (code "292") (name "unconnected-(E27B-Q-Pad9)") (class "Default")
      (node (ref "E27") (pin "9") (pinfunction "Q_9") (pintype "output"))
    )
    (net (code "293") (name "unconnected-(E28-Pad2)") (class "Default")
      (node (ref "E28") (pin "2") (pinfunction "2_2") (pintype "passive"))
    )
    (net (code "294") (name "unconnected-(E28-Pad6)") (class "Default")
      (node (ref "E28") (pin "6") (pinfunction "6_6") (pintype "passive"))
    )
    (net (code "295") (name "unconnected-(E28-Pad13)") (class "Default")
      (node (ref "E28") (pin "13") (pinfunction "13_13") (pintype "passive"))
    )
    (net (code "296") (name "unconnected-(E31A-~{Q2}-Pad6)") (class "Default")
      (node (ref "E31") (pin "6") (pinfunction "~{Q2}_6") (pintype "output"))
    )
    (net (code "297") (name "unconnected-(E31A-~{Q3}-Pad11)") (class "Default")
      (node (ref "E31") (pin "11") (pinfunction "~{Q3}_11") (pintype "output"))
    )
    (net (code "298") (name "unconnected-(E41A-O8-Pad10)") (class "Default")
      (node (ref "E41") (pin "10") (pinfunction "O8_10") (pintype "output"))
    )
    (net (code "299") (name "unconnected-(E41A-O9-Pad11)") (class "Default")
      (node (ref "E41") (pin "11") (pinfunction "O9_11") (pintype "output"))
    )
    (net (code "300") (name "unconnected-(E43A-Q-Pad5)") (class "Default")
      (node (ref "E43") (pin "5") (pinfunction "Q_5") (pintype "output"))
    )
    (net (code "301") (name "unconnected-(E43B-Q-Pad9)") (class "Default")
      (node (ref "E43") (pin "9") (pinfunction "Q_9") (pintype "output"))
    )
    (net (code "302") (name "unconnected-(E44A-QB-Pad9)") (class "Default")
      (node (ref "E44") (pin "9") (pinfunction "QB_9") (pintype "output"))
    )
    (net (code "303") (name "unconnected-(E44A-QC-Pad8)") (class "Default")
      (node (ref "E44") (pin "8") (pinfunction "QC_8") (pintype "output"))
    )
    (net (code "304") (name "unconnected-(E56B-Q-Pad9)") (class "Default")
      (node (ref "E56") (pin "9") (pinfunction "Q_9") (pintype "output"))
    )
    (net (code "305") (name "unconnected-(E57B-~{Q}-Pad8)") (class "Default")
      (node (ref "E57") (pin "8") (pinfunction "~{Q}_8") (pintype "output"))
    )
    (net (code "306") (name "unconnected-(J1-3-PadC)") (class "Default")
      (node (ref "J1") (pin "C") (pinfunction "3_C") (pintype "bidirectional"))
    )
    (net (code "307") (name "unconnected-(J1-4-PadD)") (class "Default")
      (node (ref "J1") (pin "D") (pinfunction "4_D") (pintype "bidirectional"))
    )
    (net (code "308") (name "unconnected-(J1-10-PadL)") (class "Default")
      (node (ref "J1") (pin "L") (pinfunction "10_L") (pintype "bidirectional"))
    )
    (net (code "309") (name "unconnected-(J1-12-PadN)") (class "Default")
      (node (ref "J1") (pin "N") (pinfunction "12_N") (pintype "bidirectional"))
    )
    (net (code "310") (name "unconnected-(J1-13-PadP)") (class "Default")
      (node (ref "J1") (pin "P") (pinfunction "13_P") (pintype "bidirectional"))
    )
    (net (code "311") (name "unconnected-(J1-14-PadR)") (class "Default")
      (node (ref "J1") (pin "R") (pinfunction "14_R") (pintype "bidirectional"))
    )
    (net (code "312") (name "unconnected-(J1-16-PadT)") (class "Default")
      (node (ref "J1") (pin "T") (pinfunction "16_T") (pintype "bidirectional"))
    )
    (net (code "313") (name "unconnected-(J1-17-PadU)") (class "Default")
      (node (ref "J1") (pin "U") (pinfunction "17_U") (pintype "bidirectional"))
    )
    (net (code "314") (name "unconnected-(J1-18-PadV)") (class "Default")
      (node (ref "J1") (pin "V") (pinfunction "18_V") (pintype "bidirectional"))
    )
    (net (code "315") (name "unconnected-(J1-19-PadW)") (class "Default")
      (node (ref "J1") (pin "W") (pinfunction "19_W") (pintype "bidirectional"))
    )
    (net (code "316") (name "unconnected-(J1-20-PadX)") (class "Default")
      (node (ref "J1") (pin "X") (pinfunction "20_X") (pintype "bidirectional"))
    )
    (net (code "317") (name "unconnected-(J1-22-PadZ)") (class "Default")
      (node (ref "J1") (pin "Z") (pinfunction "22_Z") (pintype "bidirectional"))
    )
    (net (code "318") (name "unconnected-(J1-24-PadBB)") (class "Default")
      (node (ref "J1") (pin "BB") (pinfunction "24_BB") (pintype "bidirectional"))
    )
    (net (code "319") (name "unconnected-(J1-25-PadCC)") (class "Default")
      (node (ref "J1") (pin "CC") (pinfunction "25_CC") (pintype "bidirectional"))
    )
    (net (code "320") (name "unconnected-(J1-28-PadFF)") (class "Default")
      (node (ref "J1") (pin "FF") (pinfunction "28_FF") (pintype "bidirectional"))
    )
    (net (code "321") (name "unconnected-(J1-29-PadHH)") (class "Default")
      (node (ref "J1") (pin "HH") (pinfunction "29_HH") (pintype "bidirectional"))
    )
    (net (code "322") (name "unconnected-(J1-30-PadJJ)") (class "Default")
      (node (ref "J1") (pin "JJ") (pinfunction "30_JJ") (pintype "bidirectional"))
    )
    (net (code "323") (name "unconnected-(J1-32-PadLL)") (class "Default")
      (node (ref "J1") (pin "LL") (pinfunction "32_LL") (pintype "bidirectional"))
    )
    (net (code "324") (name "unconnected-(J1-33-PadMM)") (class "Default")
      (node (ref "J1") (pin "MM") (pinfunction "33_MM") (pintype "bidirectional"))
    )
    (net (code "325") (name "unconnected-(J1-34-PadNN)") (class "Default")
      (node (ref "J1") (pin "NN") (pinfunction "34_NN") (pintype "bidirectional"))
    )
    (net (code "326") (name "unconnected-(J1-36-PadRR)") (class "Default")
      (node (ref "J1") (pin "RR") (pinfunction "36_RR") (pintype "bidirectional"))
    )
    (net (code "327") (name "~{LF_DECODED}") (class "Default")
      (node (ref "E26") (pin "8") (pinfunction "O_8") (pintype "output"))
      (node (ref "E57") (pin "12") (pinfunction "D_12") (pintype "input"))
      (node (ref "R37") (pin "1") (pinfunction "1_1") (pintype "passive"))
    )
    (net (code "328") (name "~{RESET_DAV}") (class "Default")
      (node (ref "E19") (pin "18") (pinfunction "/RDAV_18") (pintype "input"))
      (node (ref "E20") (pin "8") (pinfunction "~{Q}_8") (pintype "output"))
    )
    (net (code "329") (name "~{RX20MA_DATA}") (class "Default")
      (node (ref "E51") (pin "3") (pinfunction "O_3") (pintype "output"))
      (node (ref "E51") (pin "6") (pinfunction "I0_6") (pintype "input"))
      (node (ref "E54") (pin "1") (pinfunction "I0_1") (pintype "input"))
    )
    (net (code "330") (name "~{SYNC}") (class "Default")
      (node (ref "E14") (pin "3") (pinfunction "R0(2)_3") (pintype "input"))
      (node (ref "E15") (pin "2") (pinfunction "R0(1)_2") (pintype "input"))
      (node (ref "E17") (pin "3") (pinfunction "R0(2)_3") (pintype "input"))
      (node (ref "E18") (pin "2") (pinfunction "R0(1)_2") (pintype "input"))
      (node (ref "E27") (pin "8") (pinfunction "~{Q}_8") (pintype "output"))
      (node (ref "E8") (pin "3") (pinfunction "R0(2)_3") (pintype "input"))
      (node (ref "E9") (pin "6") (pinfunction "R0(1)_6") (pintype "input"))
    )
    (net (code "331") (name "~{TRANS_246}") (class "Default")
      (node (ref "E24") (pin "10") (pinfunction "I1_10") (pintype "input"))
      (node (ref "E24") (pin "11") (pinfunction "I0_11") (pintype "input"))
      (node (ref "E24") (pin "5") (pinfunction "I1_5") (pintype "input"))
      (node (ref "E24") (pin "6") (pinfunction "I0_6") (pintype "input"))
      (node (ref "E30") (pin "10") (pinfunction "I1_10") (pintype "input"))
      (node (ref "E30") (pin "11") (pinfunction "I0_11") (pintype "input"))
      (node (ref "E30") (pin "5") (pinfunction "I1_5") (pintype "input"))
      (node (ref "E30") (pin "6") (pinfunction "I0_6") (pintype "input"))
      (node (ref "R33") (pin "1") (pinfunction "1_1") (pintype "passive"))
    )
    (net (code "332") (name "~{TX_CLK}") (class "Default")
      (node (ref "E22") (pin "6") (pinfunction "W_6") (pintype "output"))
      (node (ref "E28") (pin "15") (pinfunction "15_15") (pintype "passive"))
    )
  )
)
